# whiskashisei-ver4_1.net
KiCad netlist of a schematic drawn in EAGLE
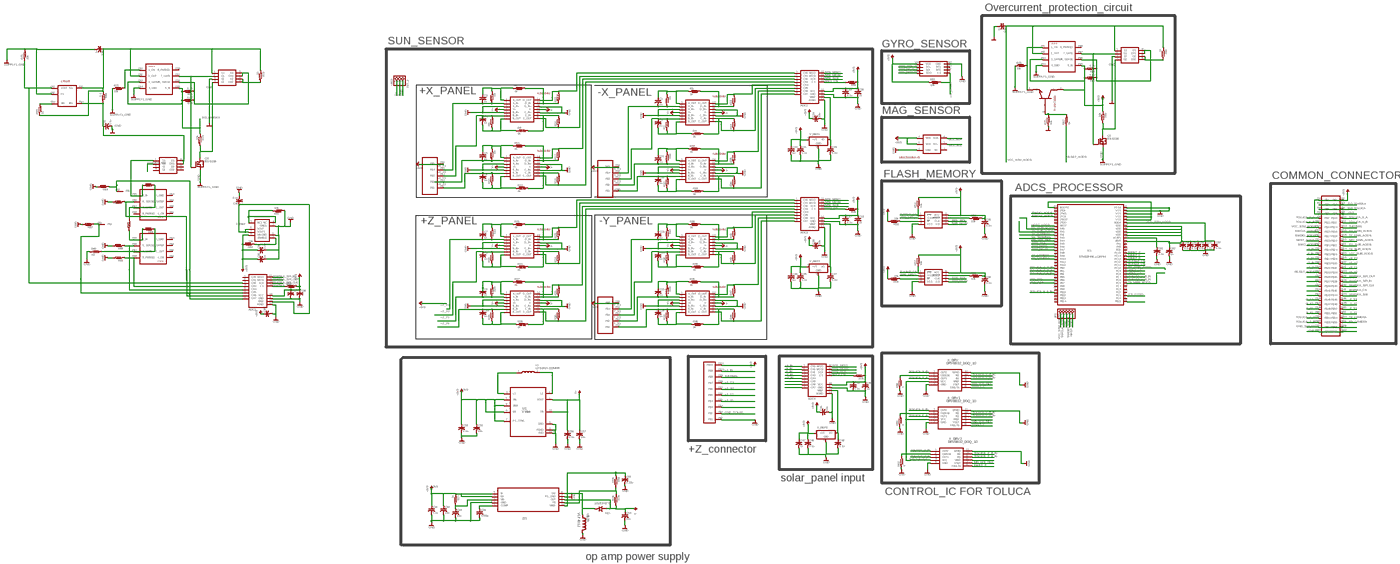
[diagram p0: schematic, sheet 1, overview]
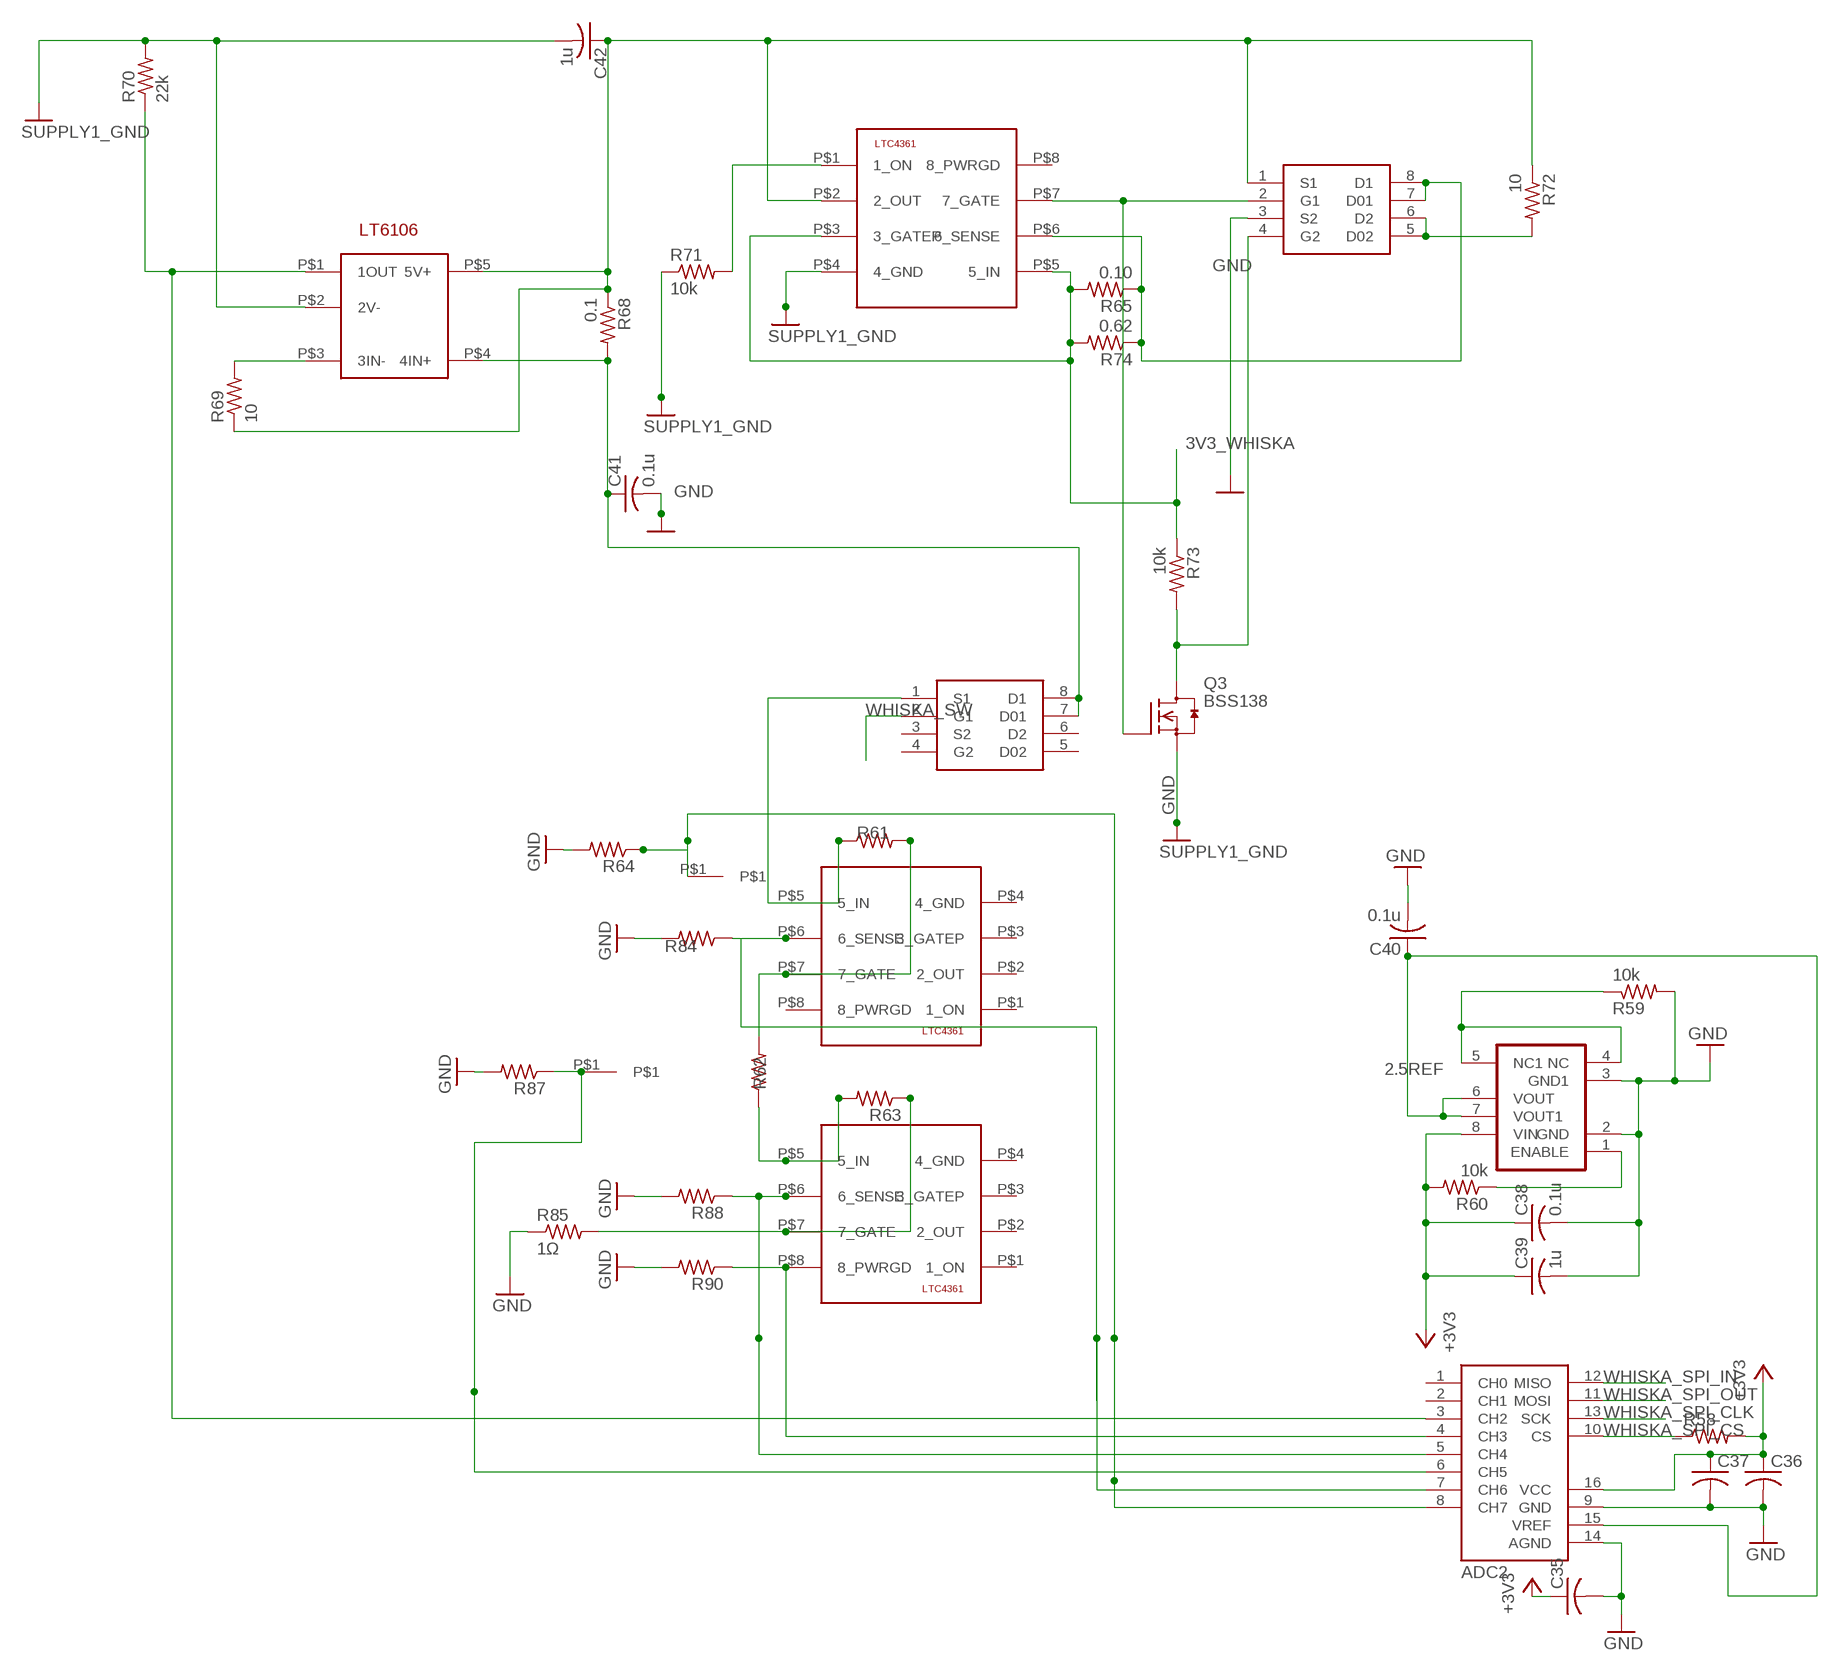
[diagram p1: schematic, sheet 1, part 1 of 4]
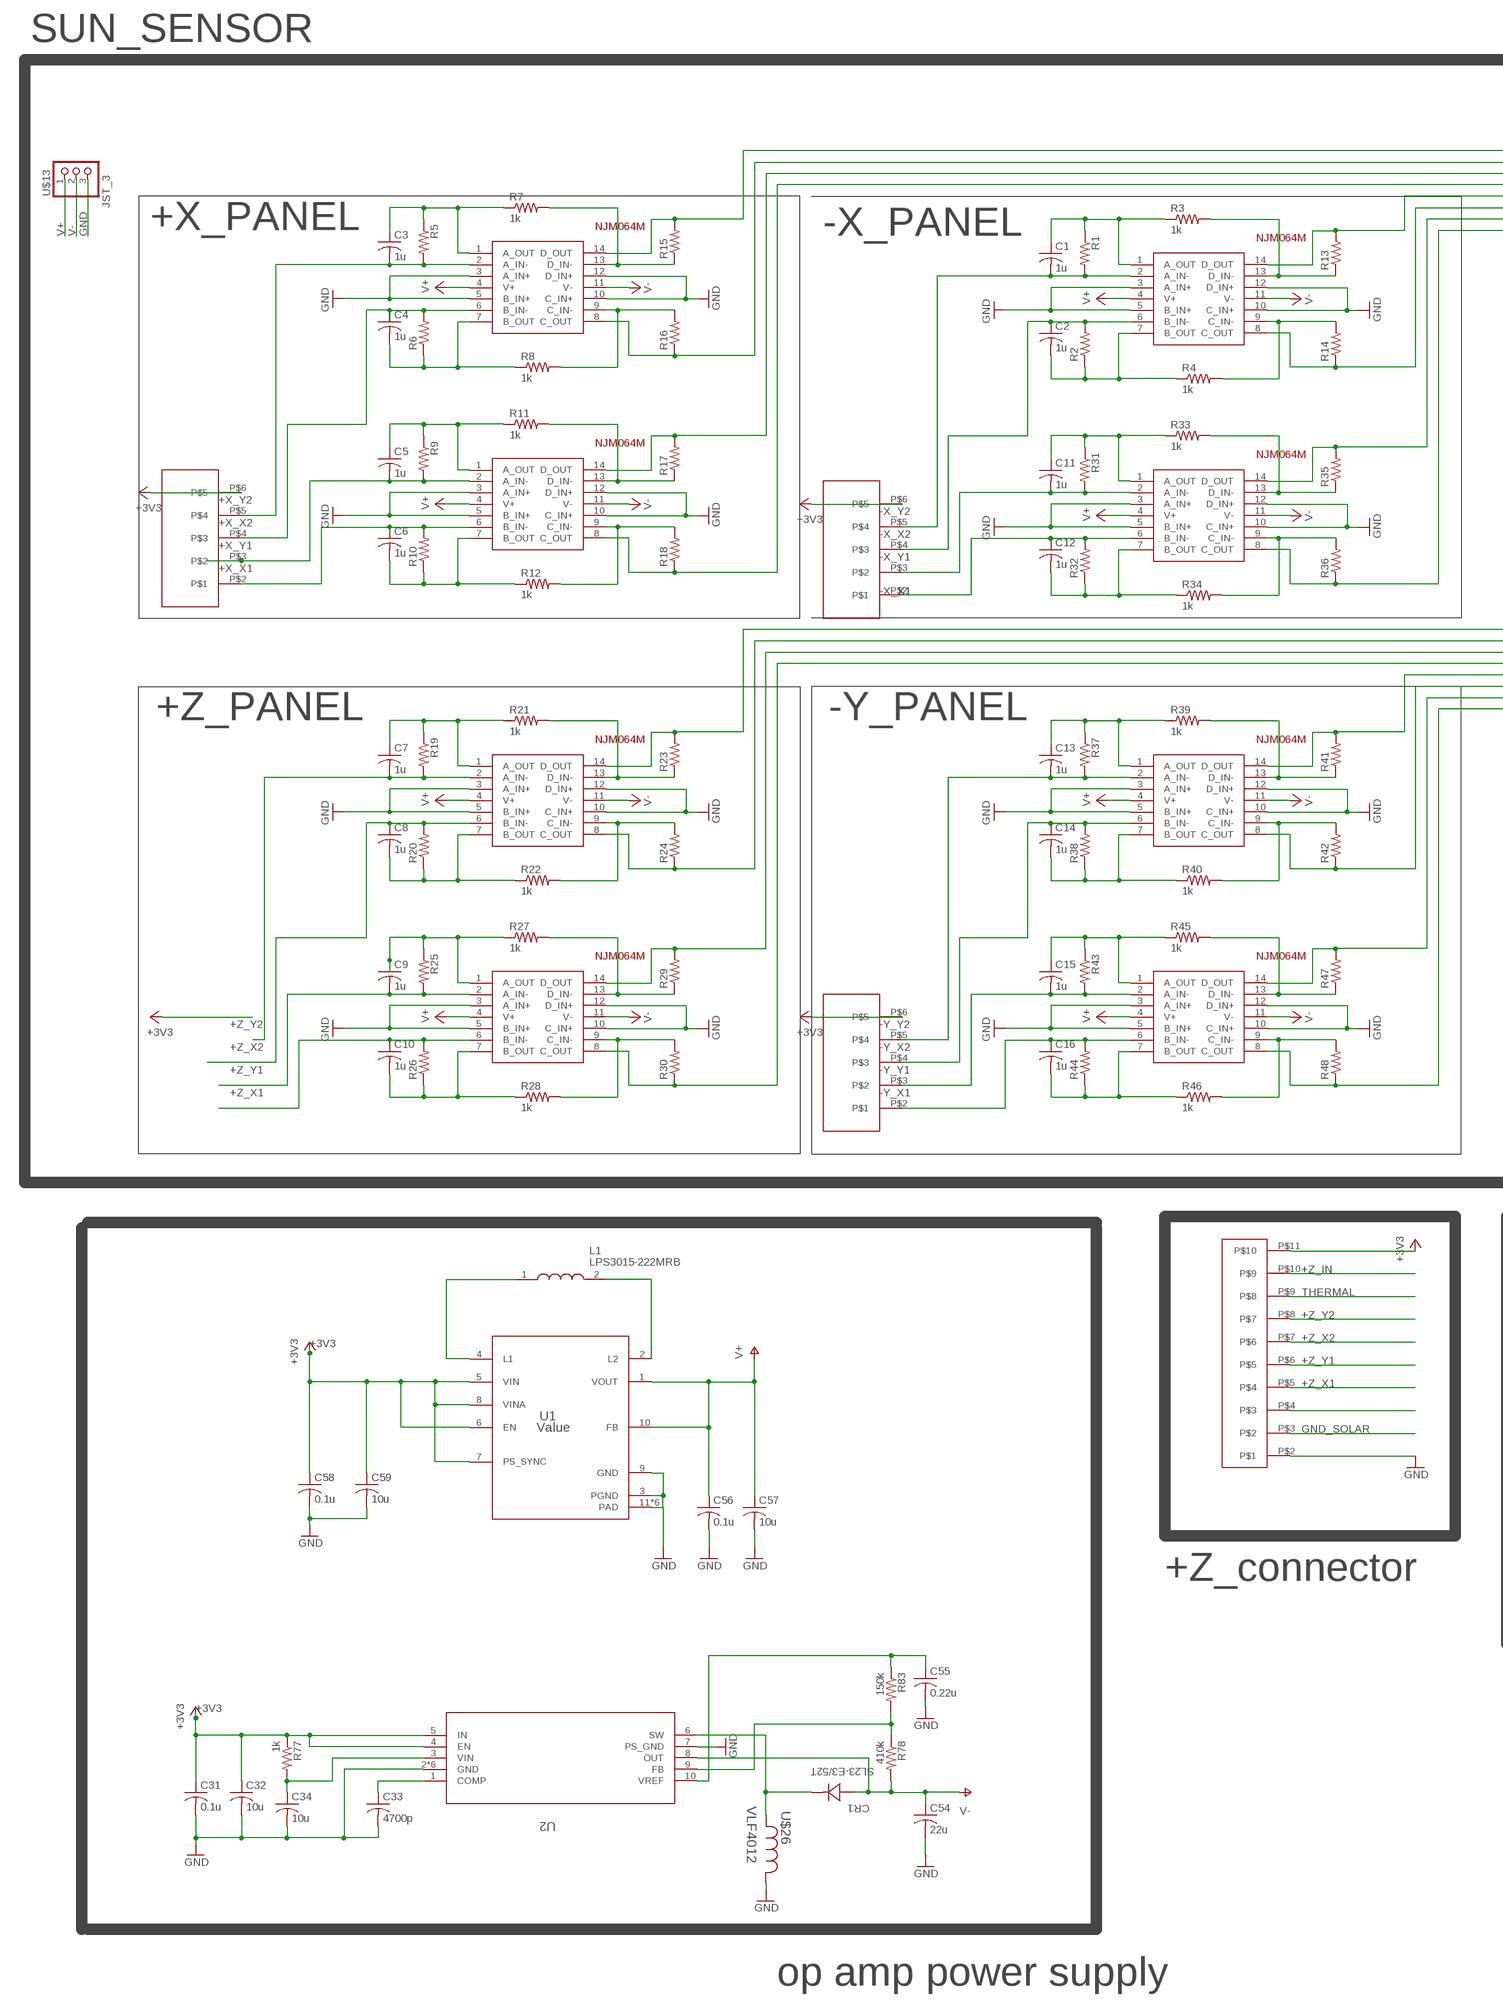
[diagram p2: schematic, sheet 1, part 2 of 4]
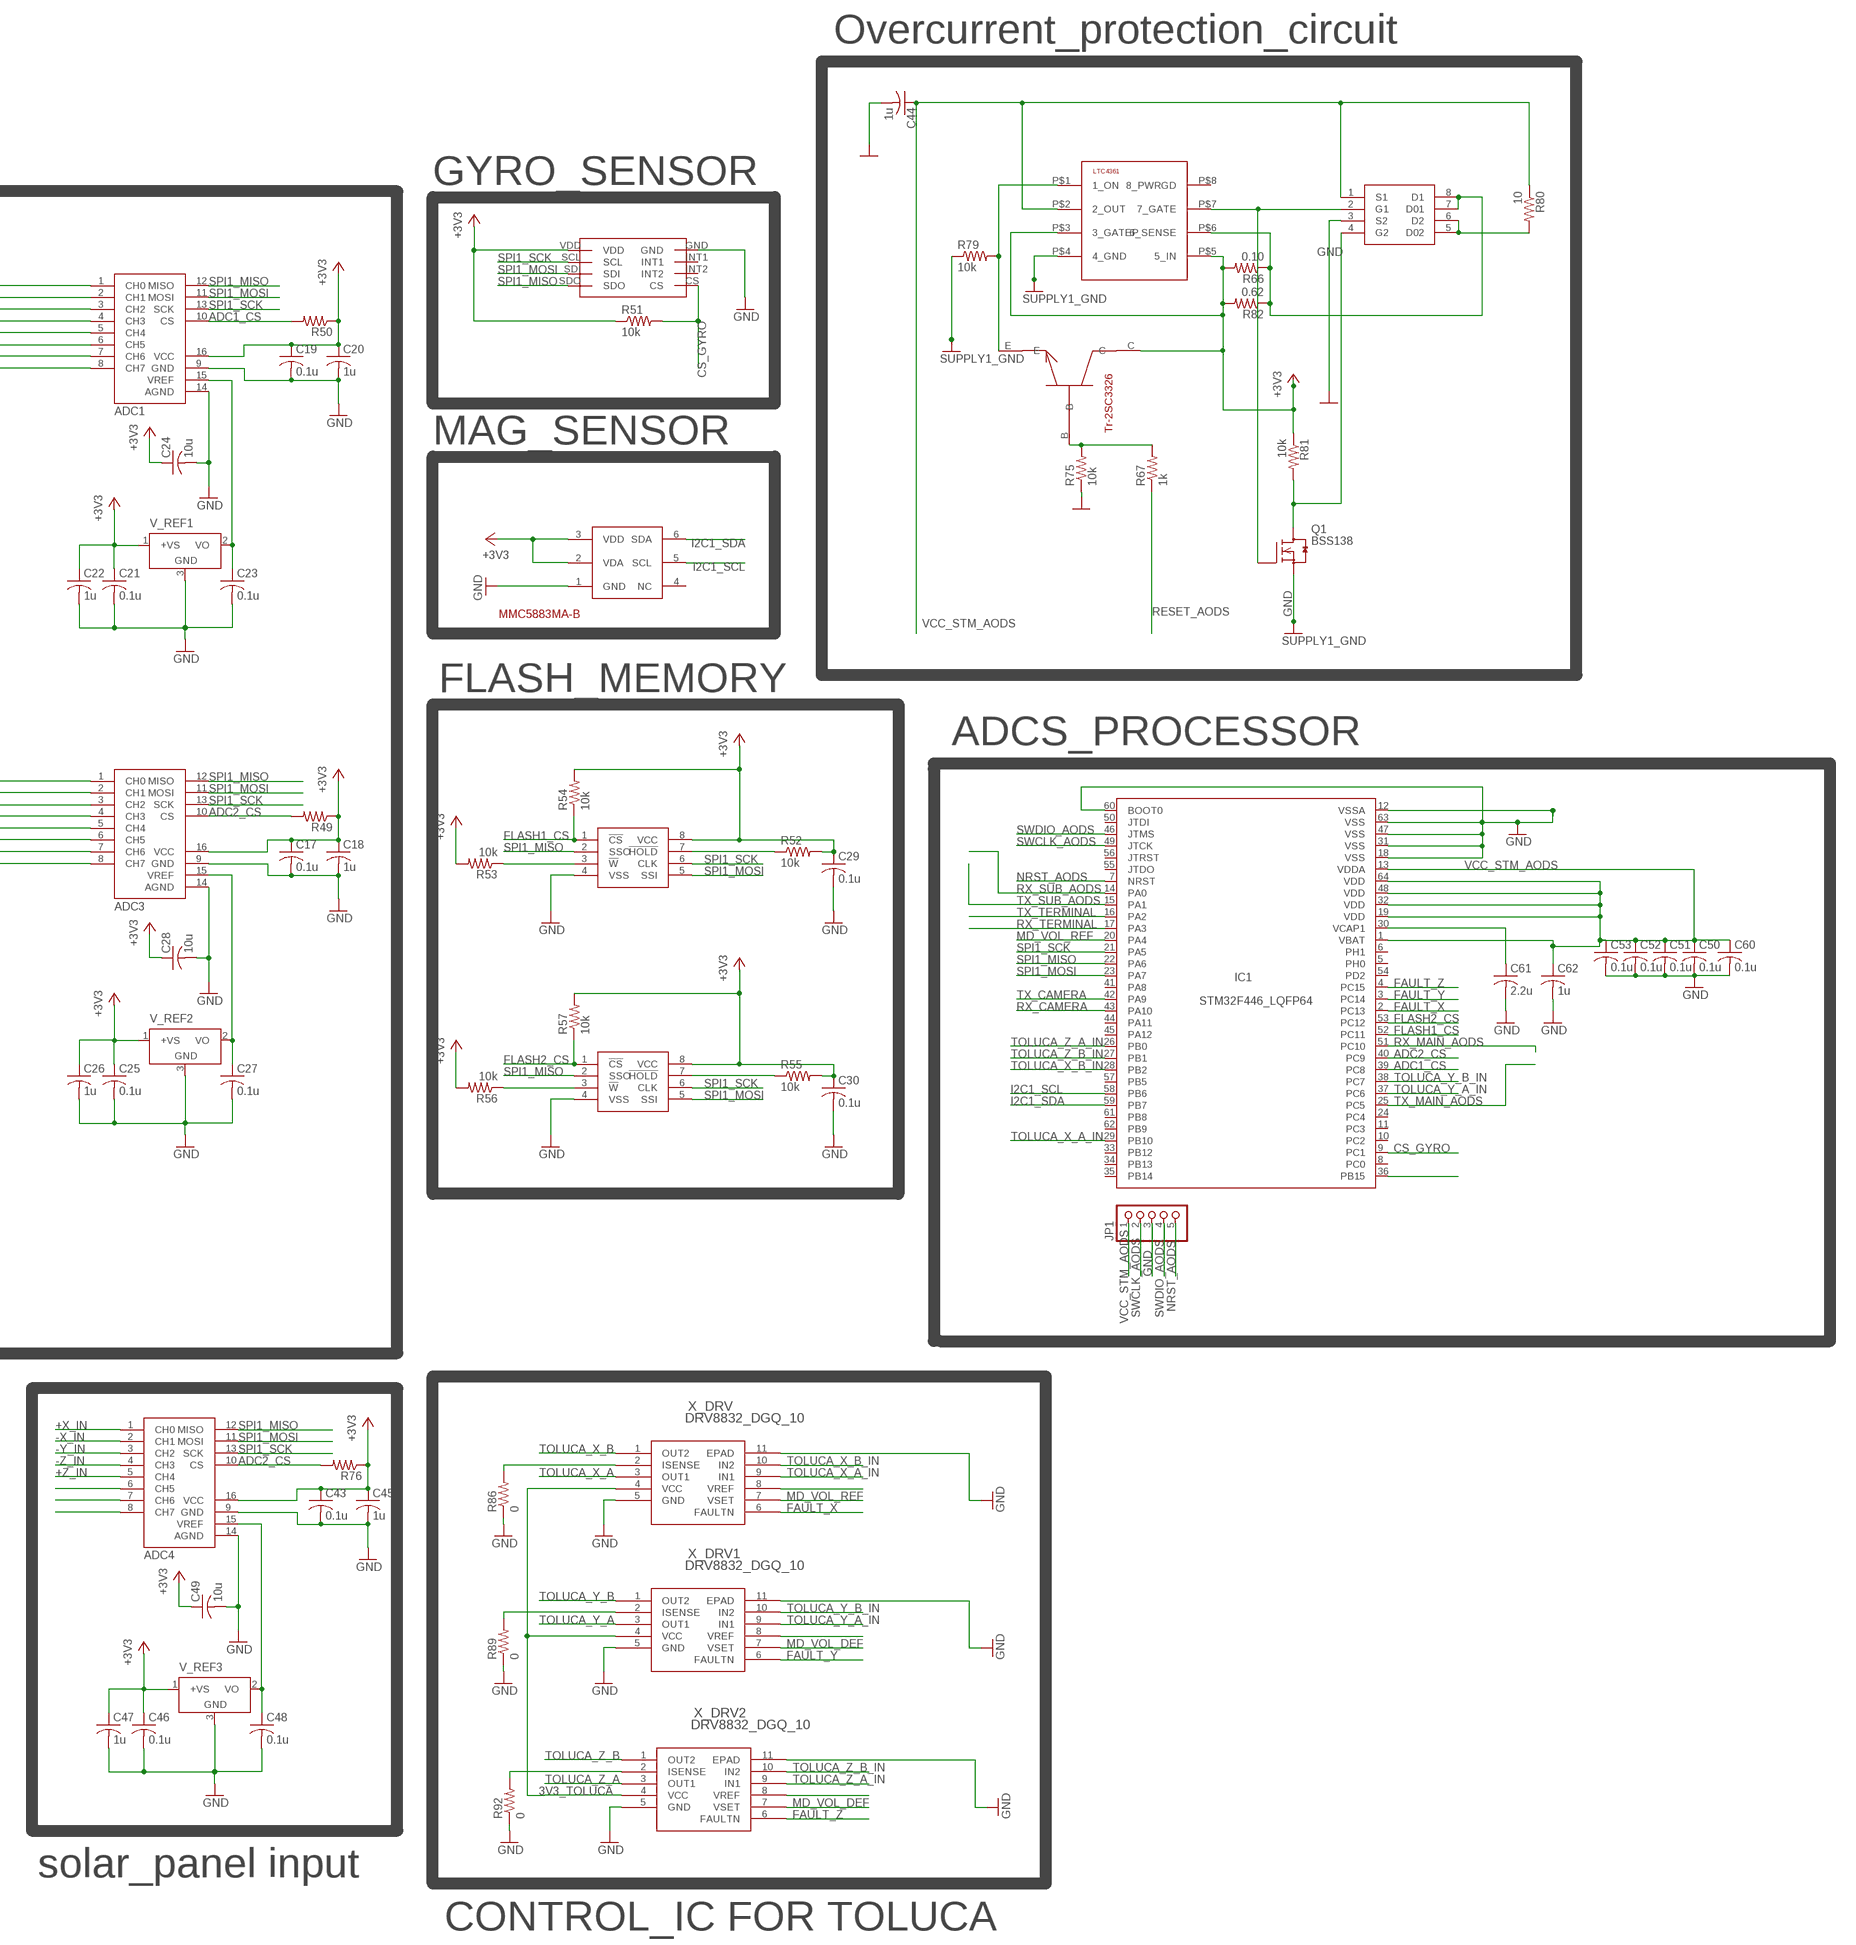
[diagram p3: schematic, sheet 1, part 3 of 4]
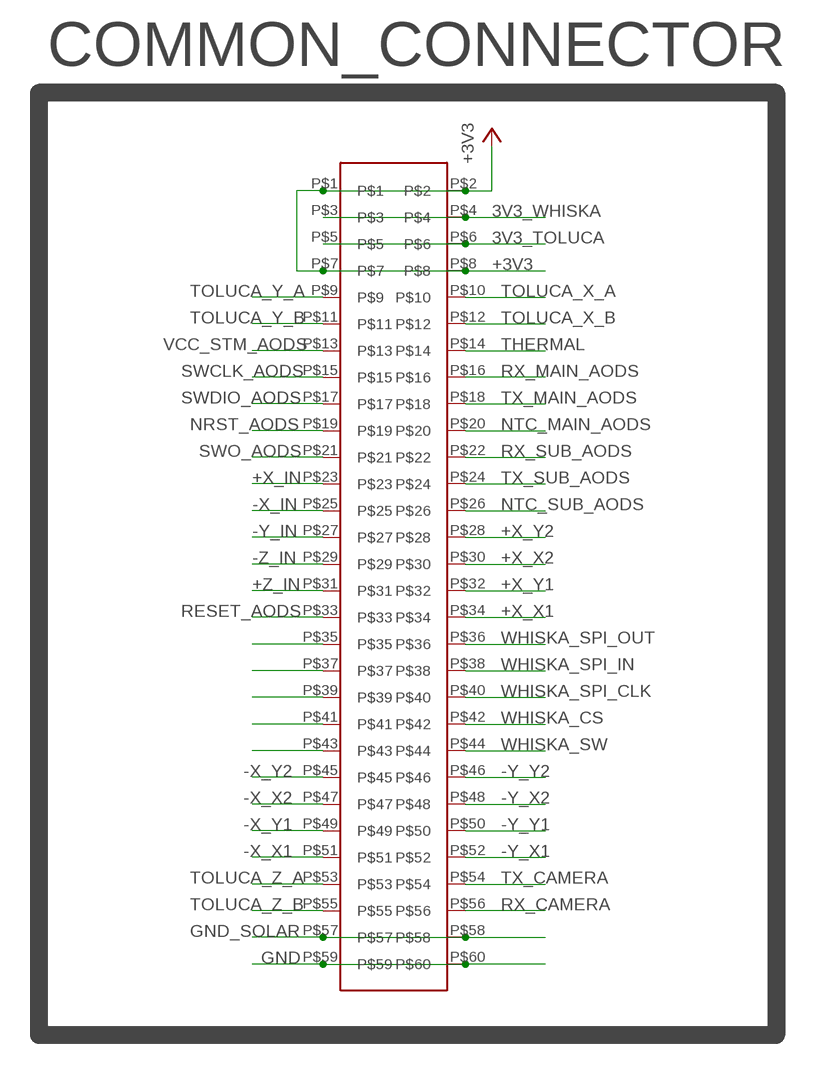
[diagram p4: schematic, sheet 1, part 4 of 4]

(export (version "E")
  (design (tool "Eeschema 10.0.6"))
  (components
    (comp (ref "ADC1")
      (value "ADC_MCP3208")
      (footprint "eagle-import:SO16")
      (libsource (lib "eagle-import") (part "ADC_MCP3208"))
    )
    (comp (ref "ADC2")
      (value "ADC_MCP3208")
      (footprint "eagle-import:SO16")
      (libsource (lib "eagle-import") (part "ADC_MCP3208"))
    )
    (comp (ref "ADC3")
      (value "ADC_MCP3208")
      (footprint "eagle-import:SO16")
      (libsource (lib "eagle-import") (part "ADC_MCP3208"))
    )
    (comp (ref "ADC4")
      (value "ADC_MCP3208")
      (footprint "eagle-import:SO16")
      (libsource (lib "eagle-import") (part "ADC_MCP3208"))
    )
    (comp (ref "C1")
      (value "1u")
      (footprint "eagle-import:C2012")
      (libsource (lib "eagle-import") (part "C-USC2012"))
    )
    (comp (ref "C2")
      (value "1u")
      (footprint "eagle-import:C2012")
      (libsource (lib "eagle-import") (part "C-USC2012"))
    )
    (comp (ref "C3")
      (value "1u")
      (footprint "eagle-import:C2012")
      (libsource (lib "eagle-import") (part "C-USC2012"))
    )
    (comp (ref "C4")
      (value "1u")
      (footprint "eagle-import:C2012")
      (libsource (lib "eagle-import") (part "C-USC2012"))
    )
    (comp (ref "C5")
      (value "1u")
      (footprint "eagle-import:C2012")
      (libsource (lib "eagle-import") (part "C-USC2012"))
    )
    (comp (ref "C6")
      (value "1u")
      (footprint "eagle-import:C2012")
      (libsource (lib "eagle-import") (part "C-USC2012"))
    )
    (comp (ref "C7")
      (value "1u")
      (footprint "eagle-import:C2012")
      (libsource (lib "eagle-import") (part "C-USC2012"))
    )
    (comp (ref "C8")
      (value "1u")
      (footprint "eagle-import:C2012")
      (libsource (lib "eagle-import") (part "C-USC2012"))
    )
    (comp (ref "C9")
      (value "1u")
      (footprint "eagle-import:C2012")
      (libsource (lib "eagle-import") (part "C-USC2012"))
    )
    (comp (ref "C10")
      (value "1u")
      (footprint "eagle-import:C2012")
      (libsource (lib "eagle-import") (part "C-USC2012"))
    )
    (comp (ref "C11")
      (value "1u")
      (footprint "eagle-import:C2012")
      (libsource (lib "eagle-import") (part "C-USC2012"))
    )
    (comp (ref "C12")
      (value "1u")
      (footprint "eagle-import:C2012")
      (libsource (lib "eagle-import") (part "C-USC2012"))
    )
    (comp (ref "C13")
      (value "1u")
      (footprint "eagle-import:C2012")
      (libsource (lib "eagle-import") (part "C-USC2012"))
    )
    (comp (ref "C14")
      (value "1u")
      (footprint "eagle-import:C2012")
      (libsource (lib "eagle-import") (part "C-USC2012"))
    )
    (comp (ref "C15")
      (value "1u")
      (footprint "eagle-import:C2012")
      (libsource (lib "eagle-import") (part "C-USC2012"))
    )
    (comp (ref "C16")
      (value "1u")
      (footprint "eagle-import:C2012")
      (libsource (lib "eagle-import") (part "C-USC2012"))
    )
    (comp (ref "C17")
      (value "0.1u")
      (footprint "eagle-import:C2012")
      (libsource (lib "eagle-import") (part "C-USC2012"))
    )
    (comp (ref "C18")
      (value "1u")
      (footprint "eagle-import:C2012")
      (libsource (lib "eagle-import") (part "C-USC2012"))
    )
    (comp (ref "C19")
      (value "0.1u")
      (footprint "eagle-import:C2012")
      (libsource (lib "eagle-import") (part "C-USC2012"))
    )
    (comp (ref "C20")
      (value "1u")
      (footprint "eagle-import:C2012")
      (libsource (lib "eagle-import") (part "C-USC2012"))
    )
    (comp (ref "C21")
      (value "0.1u")
      (footprint "eagle-import:C2012")
      (libsource (lib "eagle-import") (part "C-USC2012"))
    )
    (comp (ref "C22")
      (value "1u")
      (footprint "eagle-import:C2012")
      (libsource (lib "eagle-import") (part "C-USC2012"))
    )
    (comp (ref "C23")
      (value "0.1u")
      (footprint "eagle-import:C2012")
      (libsource (lib "eagle-import") (part "C-USC2012"))
    )
    (comp (ref "C24")
      (value "10u")
      (footprint "eagle-import:C2012")
      (libsource (lib "eagle-import") (part "C-USC2012"))
    )
    (comp (ref "C25")
      (value "0.1u")
      (footprint "eagle-import:C2012")
      (libsource (lib "eagle-import") (part "C-USC2012"))
    )
    (comp (ref "C26")
      (value "1u")
      (footprint "eagle-import:C2012")
      (libsource (lib "eagle-import") (part "C-USC2012"))
    )
    (comp (ref "C27")
      (value "0.1u")
      (footprint "eagle-import:C2012")
      (libsource (lib "eagle-import") (part "C-USC2012"))
    )
    (comp (ref "C28")
      (value "10u")
      (footprint "eagle-import:C2012")
      (libsource (lib "eagle-import") (part "C-USC2012"))
    )
    (comp (ref "C29")
      (value "0.1u")
      (footprint "eagle-import:C2012")
      (libsource (lib "eagle-import") (part "C-USC2012"))
    )
    (comp (ref "C30")
      (value "0.1u")
      (footprint "eagle-import:C2012")
      (libsource (lib "eagle-import") (part "C-USC2012"))
    )
    (comp (ref "C31")
      (value "0.1u")
      (footprint "eagle-import:C2012")
      (libsource (lib "eagle-import") (part "C-USC2012"))
    )
    (comp (ref "C32")
      (value "10u")
      (footprint "eagle-import:C2012")
      (libsource (lib "eagle-import") (part "C-USC2012"))
    )
    (comp (ref "C33")
      (value "4700p")
      (footprint "eagle-import:C2012")
      (libsource (lib "eagle-import") (part "C-USC2012"))
    )
    (comp (ref "C34")
      (value "10u")
      (footprint "eagle-import:C2012")
      (libsource (lib "eagle-import") (part "C-USC2012"))
    )
    (comp (ref "C35")
      (value "C-USC2012")
      (footprint "eagle-import:C2012")
      (libsource (lib "eagle-import") (part "C-USC2012"))
    )
    (comp (ref "C36")
      (value "C-USC2012")
      (footprint "eagle-import:C2012")
      (libsource (lib "eagle-import") (part "C-USC2012"))
    )
    (comp (ref "C37")
      (value "C-USC2012")
      (footprint "eagle-import:C2012")
      (libsource (lib "eagle-import") (part "C-USC2012"))
    )
    (comp (ref "C38")
      (value "0.1u")
      (footprint "eagle-import:C2012")
      (libsource (lib "eagle-import") (part "resistor_C-USC2012"))
    )
    (comp (ref "C39")
      (value "1u")
      (footprint "eagle-import:C2012")
      (libsource (lib "eagle-import") (part "resistor_C-USC2012"))
    )
    (comp (ref "C40")
      (value "0.1u")
      (footprint "eagle-import:C2012")
      (libsource (lib "eagle-import") (part "resistor_C-USC2012"))
    )
    (comp (ref "C41")
      (value "0.1u")
      (footprint "eagle-import:C2012")
      (libsource (lib "eagle-import") (part "resistor_C-USC2012"))
    )
    (comp (ref "C42")
      (value "1u")
      (footprint "eagle-import:C2012")
      (libsource (lib "eagle-import") (part "resistor_C-USC2012"))
    )
    (comp (ref "C43")
      (value "0.1u")
      (footprint "eagle-import:C2012")
      (libsource (lib "eagle-import") (part "C-USC2012"))
    )
    (comp (ref "C44")
      (value "1u")
      (footprint "eagle-import:C2012")
      (libsource (lib "eagle-import") (part "resistor_C-USC2012"))
    )
    (comp (ref "C45")
      (value "1u")
      (footprint "eagle-import:C2012")
      (libsource (lib "eagle-import") (part "C-USC2012"))
    )
    (comp (ref "C46")
      (value "0.1u")
      (footprint "eagle-import:C2012")
      (libsource (lib "eagle-import") (part "C-USC2012"))
    )
    (comp (ref "C47")
      (value "1u")
      (footprint "eagle-import:C2012")
      (libsource (lib "eagle-import") (part "C-USC2012"))
    )
    (comp (ref "C48")
      (value "0.1u")
      (footprint "eagle-import:C2012")
      (libsource (lib "eagle-import") (part "C-USC2012"))
    )
    (comp (ref "C49")
      (value "10u")
      (footprint "eagle-import:C2012")
      (libsource (lib "eagle-import") (part "C-USC2012"))
    )
    (comp (ref "C50")
      (value "0.1u")
      (footprint "eagle-import:C2012")
      (libsource (lib "eagle-import") (part "C-USC2012"))
    )
    (comp (ref "C51")
      (value "0.1u")
      (footprint "eagle-import:C2012")
      (libsource (lib "eagle-import") (part "C-USC2012"))
    )
    (comp (ref "C52")
      (value "0.1u")
      (footprint "eagle-import:C2012")
      (libsource (lib "eagle-import") (part "C-USC2012"))
    )
    (comp (ref "C53")
      (value "0.1u")
      (footprint "eagle-import:C2012")
      (libsource (lib "eagle-import") (part "C-USC2012"))
    )
    (comp (ref "C54")
      (value "22u")
      (footprint "eagle-import:C2012")
      (libsource (lib "eagle-import") (part "C-USC2012"))
    )
    (comp (ref "C55")
      (value "0.22u")
      (footprint "eagle-import:C2012")
      (libsource (lib "eagle-import") (part "C-USC2012"))
    )
    (comp (ref "C56")
      (value "0.1u")
      (footprint "eagle-import:C2012")
      (libsource (lib "eagle-import") (part "C-USC2012"))
    )
    (comp (ref "C57")
      (value "10u")
      (footprint "eagle-import:C2012")
      (libsource (lib "eagle-import") (part "C-USC2012"))
    )
    (comp (ref "C58")
      (value "0.1u")
      (footprint "eagle-import:C2012")
      (libsource (lib "eagle-import") (part "C-USC2012"))
    )
    (comp (ref "C59")
      (value "10u")
      (footprint "eagle-import:C2012")
      (libsource (lib "eagle-import") (part "C-USC2012"))
    )
    (comp (ref "C60")
      (value "0.1u")
      (footprint "eagle-import:C2012")
      (libsource (lib "eagle-import") (part "C-USC2012"))
    )
    (comp (ref "C61")
      (value "2.2u")
      (footprint "eagle-import:C2012")
      (libsource (lib "eagle-import") (part "C-USC2012"))
    )
    (comp (ref "C62")
      (value "1u")
      (footprint "eagle-import:C2012")
      (libsource (lib "eagle-import") (part "C-USC2012"))
    )
    (comp (ref "CR1")
      (value "SL23-E3/52T")
      (footprint "eagle-import:DIODE_DO214AA")
      (fields (field (name "MANUFACTURER_PART_NUMBER") "SL23E352T"))
      (libsource (lib "eagle-import") (part "SL23-E3/52T"))
    )
    (comp (ref "FLASH_CAM")
      (value "MP25P80")
      (footprint "eagle-import:SO-08M")
      (libsource (lib "eagle-import") (part "MP25P80"))
    )
    (comp (ref "FLASH_SENSOR")
      (value "MP25P80")
      (footprint "eagle-import:SO-08M")
      (libsource (lib "eagle-import") (part "MP25P80"))
    )
    (comp (ref "IC1")
      (value "STM32F446_LQFP64")
      (footprint "eagle-import:LQFP64_PACKAGE")
      (libsource (lib "eagle-import") (part "STM32F446_LQFP64"))
    )
    (comp (ref "JP1")
      (value "PINHD-1X5")
      (footprint "eagle-import:1X05")
      (libsource (lib "eagle-import") (part "PINHD-1X5"))
    )
    (comp (ref "L1")
      (value "LPS3015-222MRB")
      (footprint "eagle-import:LPS3015")
      (fields (field (name "MOUSER_PART_NUMBER") "994-LPS3015-222MRB"))
      (libsource (lib "eagle-import") (part "LPS3015-222MRB"))
    )
    (comp (ref "Q1")
      (value "BSS138")
      (footprint "eagle-import:SOT23")
      (libsource (lib "eagle-import") (part "BSS138"))
    )
    (comp (ref "Q3")
      (value "BSS138")
      (footprint "eagle-import:SOT23")
      (libsource (lib "eagle-import") (part "BSS138"))
    )
    (comp (ref "R1")
      (value "R-US_R2012")
      (footprint "eagle-import:R2012")
      (libsource (lib "eagle-import") (part "R-US_R2012"))
    )
    (comp (ref "R2")
      (value "R-US_R2012")
      (footprint "eagle-import:R2012")
      (libsource (lib "eagle-import") (part "R-US_R2012"))
    )
    (comp (ref "R3")
      (value "1k")
      (footprint "eagle-import:R2012")
      (libsource (lib "eagle-import") (part "R-US_R2012"))
    )
    (comp (ref "R4")
      (value "1k")
      (footprint "eagle-import:R2012")
      (libsource (lib "eagle-import") (part "R-US_R2012"))
    )
    (comp (ref "R5")
      (value "R-US_R2012")
      (footprint "eagle-import:R2012")
      (libsource (lib "eagle-import") (part "R-US_R2012"))
    )
    (comp (ref "R6")
      (value "R-US_R2012")
      (footprint "eagle-import:R2012")
      (libsource (lib "eagle-import") (part "R-US_R2012"))
    )
    (comp (ref "R7")
      (value "1k")
      (footprint "eagle-import:R2012")
      (libsource (lib "eagle-import") (part "R-US_R2012"))
    )
    (comp (ref "R8")
      (value "1k")
      (footprint "eagle-import:R2012")
      (libsource (lib "eagle-import") (part "R-US_R2012"))
    )
    (comp (ref "R9")
      (value "R-US_R2012")
      (footprint "eagle-import:R2012")
      (libsource (lib "eagle-import") (part "R-US_R2012"))
    )
    (comp (ref "R10")
      (value "R-US_R2012")
      (footprint "eagle-import:R2012")
      (libsource (lib "eagle-import") (part "R-US_R2012"))
    )
    (comp (ref "R11")
      (value "1k")
      (footprint "eagle-import:R2012")
      (libsource (lib "eagle-import") (part "R-US_R2012"))
    )
    (comp (ref "R12")
      (value "1k")
      (footprint "eagle-import:R2012")
      (libsource (lib "eagle-import") (part "R-US_R2012"))
    )
    (comp (ref "R13")
      (value "R-US_R2012")
      (footprint "eagle-import:R2012")
      (libsource (lib "eagle-import") (part "R-US_R2012"))
    )
    (comp (ref "R14")
      (value "R-US_R2012")
      (footprint "eagle-import:R2012")
      (libsource (lib "eagle-import") (part "R-US_R2012"))
    )
    (comp (ref "R15")
      (value "R-US_R2012")
      (footprint "eagle-import:R2012")
      (libsource (lib "eagle-import") (part "R-US_R2012"))
    )
    (comp (ref "R16")
      (value "R-US_R2012")
      (footprint "eagle-import:R2012")
      (libsource (lib "eagle-import") (part "R-US_R2012"))
    )
    (comp (ref "R17")
      (value "R-US_R2012")
      (footprint "eagle-import:R2012")
      (libsource (lib "eagle-import") (part "R-US_R2012"))
    )
    (comp (ref "R18")
      (value "R-US_R2012")
      (footprint "eagle-import:R2012")
      (libsource (lib "eagle-import") (part "R-US_R2012"))
    )
    (comp (ref "R19")
      (value "R-US_R2012")
      (footprint "eagle-import:R2012")
      (libsource (lib "eagle-import") (part "R-US_R2012"))
    )
    (comp (ref "R20")
      (value "R-US_R2012")
      (footprint "eagle-import:R2012")
      (libsource (lib "eagle-import") (part "R-US_R2012"))
    )
    (comp (ref "R21")
      (value "1k")
      (footprint "eagle-import:R2012")
      (libsource (lib "eagle-import") (part "R-US_R2012"))
    )
    (comp (ref "R22")
      (value "1k")
      (footprint "eagle-import:R2012")
      (libsource (lib "eagle-import") (part "R-US_R2012"))
    )
    (comp (ref "R23")
      (value "R-US_R2012")
      (footprint "eagle-import:R2012")
      (libsource (lib "eagle-import") (part "R-US_R2012"))
    )
    (comp (ref "R24")
      (value "R-US_R2012")
      (footprint "eagle-import:R2012")
      (libsource (lib "eagle-import") (part "R-US_R2012"))
    )
    (comp (ref "R25")
      (value "R-US_R2012")
      (footprint "eagle-import:R2012")
      (libsource (lib "eagle-import") (part "R-US_R2012"))
    )
    (comp (ref "R26")
      (value "R-US_R2012")
      (footprint "eagle-import:R2012")
      (libsource (lib "eagle-import") (part "R-US_R2012"))
    )
    (comp (ref "R27")
      (value "1k")
      (footprint "eagle-import:R2012")
      (libsource (lib "eagle-import") (part "R-US_R2012"))
    )
    (comp (ref "R28")
      (value "1k")
      (footprint "eagle-import:R2012")
      (libsource (lib "eagle-import") (part "R-US_R2012"))
    )
    (comp (ref "R29")
      (value "R-US_R2012")
      (footprint "eagle-import:R2012")
      (libsource (lib "eagle-import") (part "R-US_R2012"))
    )
    (comp (ref "R30")
      (value "R-US_R2012")
      (footprint "eagle-import:R2012")
      (libsource (lib "eagle-import") (part "R-US_R2012"))
    )
    (comp (ref "R31")
      (value "R-US_R2012")
      (footprint "eagle-import:R2012")
      (libsource (lib "eagle-import") (part "R-US_R2012"))
    )
    (comp (ref "R32")
      (value "R-US_R2012")
      (footprint "eagle-import:R2012")
      (libsource (lib "eagle-import") (part "R-US_R2012"))
    )
    (comp (ref "R33")
      (value "1k")
      (footprint "eagle-import:R2012")
      (libsource (lib "eagle-import") (part "R-US_R2012"))
    )
    (comp (ref "R34")
      (value "1k")
      (footprint "eagle-import:R2012")
      (libsource (lib "eagle-import") (part "R-US_R2012"))
    )
    (comp (ref "R35")
      (value "R-US_R2012")
      (footprint "eagle-import:R2012")
      (libsource (lib "eagle-import") (part "R-US_R2012"))
    )
    (comp (ref "R36")
      (value "R-US_R2012")
      (footprint "eagle-import:R2012")
      (libsource (lib "eagle-import") (part "R-US_R2012"))
    )
    (comp (ref "R37")
      (value "R-US_R2012")
      (footprint "eagle-import:R2012")
      (libsource (lib "eagle-import") (part "R-US_R2012"))
    )
    (comp (ref "R38")
      (value "R-US_R2012")
      (footprint "eagle-import:R2012")
      (libsource (lib "eagle-import") (part "R-US_R2012"))
    )
    (comp (ref "R39")
      (value "1k")
      (footprint "eagle-import:R2012")
      (libsource (lib "eagle-import") (part "R-US_R2012"))
    )
    (comp (ref "R40")
      (value "1k")
      (footprint "eagle-import:R2012")
      (libsource (lib "eagle-import") (part "R-US_R2012"))
    )
    (comp (ref "R41")
      (value "R-US_R2012")
      (footprint "eagle-import:R2012")
      (libsource (lib "eagle-import") (part "R-US_R2012"))
    )
    (comp (ref "R42")
      (value "R-US_R2012")
      (footprint "eagle-import:R2012")
      (libsource (lib "eagle-import") (part "R-US_R2012"))
    )
    (comp (ref "R43")
      (value "R-US_R2012")
      (footprint "eagle-import:R2012")
      (libsource (lib "eagle-import") (part "R-US_R2012"))
    )
    (comp (ref "R44")
      (value "R-US_R2012")
      (footprint "eagle-import:R2012")
      (libsource (lib "eagle-import") (part "R-US_R2012"))
    )
    (comp (ref "R45")
      (value "1k")
      (footprint "eagle-import:R2012")
      (libsource (lib "eagle-import") (part "R-US_R2012"))
    )
    (comp (ref "R46")
      (value "1k")
      (footprint "eagle-import:R2012")
      (libsource (lib "eagle-import") (part "R-US_R2012"))
    )
    (comp (ref "R47")
      (value "R-US_R2012")
      (footprint "eagle-import:R2012")
      (libsource (lib "eagle-import") (part "R-US_R2012"))
    )
    (comp (ref "R48")
      (value "R-US_R2012")
      (footprint "eagle-import:R2012")
      (libsource (lib "eagle-import") (part "R-US_R2012"))
    )
    (comp (ref "R49")
      (value "R-US_R2012")
      (footprint "eagle-import:R2012")
      (libsource (lib "eagle-import") (part "R-US_R2012"))
    )
    (comp (ref "R50")
      (value "R-US_R2012")
      (footprint "eagle-import:R2012")
      (libsource (lib "eagle-import") (part "R-US_R2012"))
    )
    (comp (ref "R51")
      (value "10k")
      (footprint "eagle-import:R2012")
      (libsource (lib "eagle-import") (part "R-US_R2012"))
    )
    (comp (ref "R52")
      (value "10k")
      (footprint "eagle-import:R2012")
      (libsource (lib "eagle-import") (part "R-US_R2012"))
    )
    (comp (ref "R53")
      (value "10k")
      (footprint "eagle-import:R2012")
      (libsource (lib "eagle-import") (part "R-US_R2012"))
    )
    (comp (ref "R54")
      (value "10k")
      (footprint "eagle-import:R2012")
      (libsource (lib "eagle-import") (part "R-US_R2012"))
    )
    (comp (ref "R55")
      (value "10k")
      (footprint "eagle-import:R2012")
      (libsource (lib "eagle-import") (part "R-US_R2012"))
    )
    (comp (ref "R56")
      (value "10k")
      (footprint "eagle-import:R2012")
      (libsource (lib "eagle-import") (part "R-US_R2012"))
    )
    (comp (ref "R57")
      (value "10k")
      (footprint "eagle-import:R2012")
      (libsource (lib "eagle-import") (part "R-US_R2012"))
    )
    (comp (ref "R58")
      (value "R-US_R2012")
      (footprint "eagle-import:R2012")
      (libsource (lib "eagle-import") (part "R-US_R2012"))
    )
    (comp (ref "R59")
      (value "10k")
      (footprint "eagle-import:R2012")
      (libsource (lib "eagle-import") (part "resistor_R-US_R2012"))
    )
    (comp (ref "R60")
      (value "10k")
      (footprint "eagle-import:R2012")
      (libsource (lib "eagle-import") (part "resistor_R-US_R2012"))
    )
    (comp (ref "R61")
      (value "R-US_R2012")
      (footprint "eagle-import:R2012")
      (libsource (lib "eagle-import") (part "R-US_R2012"))
    )
    (comp (ref "R62")
      (value "R-US_R2012")
      (footprint "eagle-import:R2012")
      (libsource (lib "eagle-import") (part "R-US_R2012"))
    )
    (comp (ref "R63")
      (value "R-US_R2012")
      (footprint "eagle-import:R2012")
      (libsource (lib "eagle-import") (part "R-US_R2012"))
    )
    (comp (ref "R64")
      (value "R-US_R2012")
      (footprint "eagle-import:R2012")
      (libsource (lib "eagle-import") (part "R-US_R2012"))
    )
    (comp (ref "R65")
      (value "0.10")
      (footprint "eagle-import:R2012")
      (libsource (lib "eagle-import") (part "resistor_R-US_R2012"))
    )
    (comp (ref "R66")
      (value "0.10")
      (footprint "eagle-import:R2012")
      (libsource (lib "eagle-import") (part "resistor_R-US_R2012"))
    )
    (comp (ref "R67")
      (value "1k")
      (footprint "eagle-import:R2012")
      (libsource (lib "eagle-import") (part "resistor_R-US_R2012"))
    )
    (comp (ref "R68")
      (value "0.1")
      (footprint "eagle-import:R2012")
      (libsource (lib "eagle-import") (part "resistor_R-US_R2012"))
    )
    (comp (ref "R69")
      (value "10")
      (footprint "eagle-import:R2012")
      (libsource (lib "eagle-import") (part "resistor_R-US_R2012"))
    )
    (comp (ref "R70")
      (value "22k")
      (footprint "eagle-import:R2012")
      (libsource (lib "eagle-import") (part "resistor_R-US_R2012"))
    )
    (comp (ref "R71")
      (value "10k")
      (footprint "eagle-import:R2012")
      (libsource (lib "eagle-import") (part "resistor_R-US_R2012"))
    )
    (comp (ref "R72")
      (value "10")
      (footprint "eagle-import:R2012")
      (libsource (lib "eagle-import") (part "resistor_R-US_R2012"))
    )
    (comp (ref "R73")
      (value "10k")
      (footprint "eagle-import:R2012")
      (libsource (lib "eagle-import") (part "resistor_R-US_R2012"))
    )
    (comp (ref "R74")
      (value "0.62")
      (footprint "eagle-import:R2012")
      (libsource (lib "eagle-import") (part "resistor_R-US_R2012"))
    )
    (comp (ref "R75")
      (value "10k")
      (footprint "eagle-import:R2012")
      (libsource (lib "eagle-import") (part "resistor_R-US_R2012"))
    )
    (comp (ref "R76")
      (value "R-US_R2012")
      (footprint "eagle-import:R2012")
      (libsource (lib "eagle-import") (part "R-US_R2012"))
    )
    (comp (ref "R77")
      (value "1k")
      (footprint "eagle-import:R2012")
      (libsource (lib "eagle-import") (part "R-US_R2012"))
    )
    (comp (ref "R78")
      (value "410k")
      (footprint "eagle-import:R2012")
      (libsource (lib "eagle-import") (part "R-US_R2012"))
    )
    (comp (ref "R79")
      (value "10k")
      (footprint "eagle-import:R2012")
      (libsource (lib "eagle-import") (part "resistor_R-US_R2012"))
    )
    (comp (ref "R80")
      (value "10")
      (footprint "eagle-import:R2012")
      (libsource (lib "eagle-import") (part "resistor_R-US_R2012"))
    )
    (comp (ref "R81")
      (value "10k")
      (footprint "eagle-import:R2012")
      (libsource (lib "eagle-import") (part "resistor_R-US_R2012"))
    )
    (comp (ref "R82")
      (value "0.62")
      (footprint "eagle-import:R2012")
      (libsource (lib "eagle-import") (part "resistor_R-US_R2012"))
    )
    (comp (ref "R83")
      (value "150k")
      (footprint "eagle-import:R2012")
      (libsource (lib "eagle-import") (part "R-US_R2012"))
    )
    (comp (ref "R84")
      (value "R-US_R2012")
      (footprint "eagle-import:R2012")
      (libsource (lib "eagle-import") (part "R-US_R2012"))
    )
    (comp (ref "R85")
      (value "1Ω")
      (footprint "eagle-import:R2012")
      (libsource (lib "eagle-import") (part "R-US_R2012"))
    )
    (comp (ref "R86")
      (value "0")
      (footprint "eagle-import:R2012")
      (libsource (lib "eagle-import") (part "R-US_R2012"))
    )
    (comp (ref "R87")
      (value "R-US_R2012")
      (footprint "eagle-import:R2012")
      (libsource (lib "eagle-import") (part "R-US_R2012"))
    )
    (comp (ref "R88")
      (value "R-US_R2012")
      (footprint "eagle-import:R2012")
      (libsource (lib "eagle-import") (part "R-US_R2012"))
    )
    (comp (ref "R89")
      (value "0")
      (footprint "eagle-import:R2012")
      (libsource (lib "eagle-import") (part "R-US_R2012"))
    )
    (comp (ref "R90")
      (value "R-US_R2012")
      (footprint "eagle-import:R2012")
      (libsource (lib "eagle-import") (part "R-US_R2012"))
    )
    (comp (ref "R92")
      (value "0")
      (footprint "eagle-import:R2012")
      (libsource (lib "eagle-import") (part "R-US_R2012"))
    )
    (comp (ref "U$1")
      (value "1.27_60")
      (footprint "eagle-import:1.27_60")
      (libsource (lib "eagle-import") (part "1.27_60"))
    )
    (comp (ref "U$3")
      (value "MMC5883MA-B")
      (footprint "eagle-import:MMC5883MA-B")
      (libsource (lib "eagle-import") (part "MMC5883MA-B"))
    )
    (comp (ref "U$4")
      (value "L3GD20_SET")
      (footprint "eagle-import:L3GD20_SET")
      (libsource (lib "eagle-import") (part "L3GD20_SET"))
    )
    (comp (ref "U$5")
      (value "NJM064M")
      (footprint "eagle-import:NJM064M")
      (libsource (lib "eagle-import") (part "NJM064M"))
    )
    (comp (ref "U$6")
      (value "NJM064M")
      (footprint "eagle-import:NJM064M")
      (libsource (lib "eagle-import") (part "NJM064M"))
    )
    (comp (ref "U$7")
      (value "NJM064M")
      (footprint "eagle-import:NJM064M")
      (libsource (lib "eagle-import") (part "NJM064M"))
    )
    (comp (ref "U$8")
      (value "NJM064M")
      (footprint "eagle-import:NJM064M")
      (libsource (lib "eagle-import") (part "NJM064M"))
    )
    (comp (ref "U$9")
      (value "NJM064M")
      (footprint "eagle-import:NJM064M")
      (libsource (lib "eagle-import") (part "NJM064M"))
    )
    (comp (ref "U$10")
      (value "NJM064M")
      (footprint "eagle-import:NJM064M")
      (libsource (lib "eagle-import") (part "NJM064M"))
    )
    (comp (ref "U$11")
      (value "NJM064M")
      (footprint "eagle-import:NJM064M")
      (libsource (lib "eagle-import") (part "NJM064M"))
    )
    (comp (ref "U$12")
      (value "NJM064M")
      (footprint "eagle-import:NJM064M")
      (libsource (lib "eagle-import") (part "NJM064M"))
    )
    (comp (ref "U$13")
      (value "JST_3")
      (footprint "eagle-import:JST_3")
      (libsource (lib "eagle-import") (part "JST_3"))
    )
    (comp (ref "U$14")
      (value "ADR3525")
      (footprint "eagle-import:ADR3525")
      (libsource (lib "eagle-import") (part "ADR3525"))
    )
    (comp (ref "U$15")
      (value "LTC4361")
      (footprint "eagle-import:LTC4361_2")
      (libsource (lib "eagle-import") (part "LTC4361"))
    )
    (comp (ref "U$16")
      (value "IRF7910")
      (footprint "eagle-import:SO-08")
      (libsource (lib "eagle-import") (part "IRF7910"))
    )
    (comp (ref "U$17")
      (value "LTC4361")
      (footprint "eagle-import:LTC4361_2")
      (libsource (lib "eagle-import") (part "LTC4361"))
    )
    (comp (ref "U$18")
      (value "LT6106")
      (footprint "eagle-import:LT6106")
      (libsource (lib "eagle-import") (part "LT6106"))
    )
    (comp (ref "U$19")
      (value "IRF7910")
      (footprint "eagle-import:SO-08")
      (libsource (lib "eagle-import") (part "IRF7910"))
    )
    (comp (ref "U$20")
      (value "TR-NPN-2SC3326")
      (footprint "eagle-import:TR-NPN-2SC3326")
      (libsource (lib "eagle-import") (part "TR-NPN-2SC3326"))
    )
    (comp (ref "U$21")
      (value "JST_1MM_10")
      (footprint "eagle-import:JST_1MM_10")
      (libsource (lib "eagle-import") (part "JST_1MM_10"))
    )
    (comp (ref "U$22")
      (value "IRF7910")
      (footprint "eagle-import:SO-08")
      (libsource (lib "eagle-import") (part "IRF7910"))
    )
    (comp (ref "U$23")
      (value "LTC4361")
      (footprint "eagle-import:LTC4361_2")
      (libsource (lib "eagle-import") (part "LTC4361"))
    )
    (comp (ref "U$26")
      (value "VLF4012")
      (footprint "eagle-import:IND_4012")
      (libsource (lib "eagle-import") (part "VLF4012"))
    )
    (comp (ref "U$27")
      (value "LTC4361")
      (footprint "eagle-import:LTC4361_2")
      (libsource (lib "eagle-import") (part "LTC4361"))
    )
    (comp (ref "U$31")
      (value "JST_1MM_5")
      (footprint "eagle-import:JST_1MM_5")
      (libsource (lib "eagle-import") (part "JST_1MM_5"))
    )
    (comp (ref "U$32")
      (value "JST_1MM_5")
      (footprint "eagle-import:JST_1MM_5")
      (libsource (lib "eagle-import") (part "JST_1MM_5"))
    )
    (comp (ref "U$34")
      (value "JST_1MM_5")
      (footprint "eagle-import:JST_1MM_5")
      (libsource (lib "eagle-import") (part "JST_1MM_5"))
    )
    (comp (ref "U1")
      (value "Value")
      (footprint "eagle-import:DRC0010A")
      (fields (field (name "MANUFACTURER") "Texas Instruments") (field (name "PARTNUMBER") "TPS63000DRC"))
      (libsource (lib "eagle-import") (part "TPS63000DRCR"))
    )
    (comp (ref "U2")
      (value "TPS63700DRCRG4")
      (footprint "eagle-import:DRC10_2P4X1P65")
      (libsource (lib "eagle-import") (part "TPS63700DRCRG4"))
    )
    (comp (ref "V_REF1")
      (value "LM50")
      (footprint "eagle-import:SOT23")
      (libsource (lib "eagle-import") (part "LM50"))
    )
    (comp (ref "V_REF2")
      (value "LM50")
      (footprint "eagle-import:SOT23")
      (libsource (lib "eagle-import") (part "LM50"))
    )
    (comp (ref "V_REF3")
      (value "LM50")
      (footprint "eagle-import:SOT23")
      (libsource (lib "eagle-import") (part "LM50"))
    )
    (comp (ref "WHISKAPAD1")
      (value "WHISKAPAD")
      (footprint "eagle-import:LTC4361_2")
      (libsource (lib "eagle-import") (part "WHISKAPAD"))
    )
    (comp (ref "WHISKAPAD2")
      (value "WHISKAPAD")
      (footprint "eagle-import:LTC4361_2")
      (libsource (lib "eagle-import") (part "WHISKAPAD"))
    )
    (comp (ref "X_DRV")
      (value "DRV8832_DGQ_10")
      (footprint "eagle-import:DGQ10_2P18X1P72")
      (fields
        (field (name "GENERIC_PART_NUMBER") "DRV8832")
        (field (name "MANUFACTURER") "Texas Instruments")
        (field (name "MANUFACTURER_PART_NUMBER") "drv8832_dgq_10")
      )
      (libsource (lib "eagle-import") (part "DRV8832_DGQ_10"))
    )
    (comp (ref "X_DRV1")
      (value "DRV8832_DGQ_10")
      (footprint "eagle-import:DGQ10_2P18X1P72")
      (fields
        (field (name "GENERIC_PART_NUMBER") "DRV8832")
        (field (name "MANUFACTURER") "Texas Instruments")
        (field (name "MANUFACTURER_PART_NUMBER") "drv8832_dgq_10")
      )
      (libsource (lib "eagle-import") (part "DRV8832_DGQ_10"))
    )
    (comp (ref "X_DRV2")
      (value "DRV8832_DGQ_10")
      (footprint "eagle-import:DGQ10_2P18X1P72")
      (fields
        (field (name "GENERIC_PART_NUMBER") "DRV8832")
        (field (name "MANUFACTURER") "Texas Instruments")
        (field (name "MANUFACTURER_PART_NUMBER") "drv8832_dgq_10")
      )
      (libsource (lib "eagle-import") (part "DRV8832_DGQ_10"))
    )
  )
  (nets
    (net (code "1") (name "+3V3") (class "Default")
      (node (ref "ADC1") (pin "16") (pinfunction "VCC_16") (pintype "power_in"))
      (node (ref "ADC2") (pin "16") (pinfunction "VCC_16") (pintype "power_in"))
      (node (ref "ADC3") (pin "16") (pinfunction "VCC_16") (pintype "power_in"))
      (node (ref "ADC4") (pin "16") (pinfunction "VCC_16") (pintype "power_in"))
      (node (ref "C17") (pin "1") (pinfunction "1_1") (pintype "passive"))
      (node (ref "C18") (pin "1") (pinfunction "1_1") (pintype "passive"))
      (node (ref "C19") (pin "1") (pinfunction "1_1") (pintype "passive"))
      (node (ref "C20") (pin "1") (pinfunction "1_1") (pintype "passive"))
      (node (ref "C21") (pin "1") (pinfunction "1_1") (pintype "passive"))
      (node (ref "C22") (pin "1") (pinfunction "1_1") (pintype "passive"))
      (node (ref "C24") (pin "1") (pinfunction "1_1") (pintype "passive"))
      (node (ref "C25") (pin "1") (pinfunction "1_1") (pintype "passive"))
      (node (ref "C26") (pin "1") (pinfunction "1_1") (pintype "passive"))
      (node (ref "C28") (pin "1") (pinfunction "1_1") (pintype "passive"))
      (node (ref "C29") (pin "1") (pinfunction "1_1") (pintype "passive"))
      (node (ref "C30") (pin "1") (pinfunction "1_1") (pintype "passive"))
      (node (ref "C31") (pin "1") (pinfunction "1_1") (pintype "passive"))
      (node (ref "C32") (pin "1") (pinfunction "1_1") (pintype "passive"))
      (node (ref "C35") (pin "1") (pinfunction "1_1") (pintype "passive"))
      (node (ref "C36") (pin "1") (pinfunction "1_1") (pintype "passive"))
      (node (ref "C37") (pin "1") (pinfunction "1_1") (pintype "passive"))
      (node (ref "C38") (pin "1") (pinfunction "1_1") (pintype "passive"))
      (node (ref "C39") (pin "1") (pinfunction "1_1") (pintype "passive"))
      (node (ref "C43") (pin "1") (pinfunction "1_1") (pintype "passive"))
      (node (ref "C45") (pin "1") (pinfunction "1_1") (pintype "passive"))
      (node (ref "C46") (pin "1") (pinfunction "1_1") (pintype "passive"))
      (node (ref "C47") (pin "1") (pinfunction "1_1") (pintype "passive"))
      (node (ref "C49") (pin "1") (pinfunction "1_1") (pintype "passive"))
      (node (ref "C58") (pin "1") (pinfunction "1_1") (pintype "passive"))
      (node (ref "C59") (pin "1") (pinfunction "1_1") (pintype "passive"))
      (node (ref "FLASH_CAM") (pin "8") (pinfunction "VCC_8") (pintype "power_in"))
      (node (ref "FLASH_SENSOR") (pin "8") (pinfunction "VCC_8") (pintype "power_in"))
      (node (ref "R49") (pin "1") (pinfunction "1_1") (pintype "passive"))
      (node (ref "R50") (pin "1") (pinfunction "1_1") (pintype "passive"))
      (node (ref "R51") (pin "1") (pinfunction "1_1") (pintype "passive"))
      (node (ref "R52") (pin "2") (pinfunction "2_2") (pintype "passive"))
      (node (ref "R53") (pin "2") (pinfunction "2_2") (pintype "passive"))
      (node (ref "R54") (pin "2") (pinfunction "2_2") (pintype "passive"))
      (node (ref "R55") (pin "2") (pinfunction "2_2") (pintype "passive"))
      (node (ref "R56") (pin "2") (pinfunction "2_2") (pintype "passive"))
      (node (ref "R57") (pin "2") (pinfunction "2_2") (pintype "passive"))
      (node (ref "R58") (pin "2") (pinfunction "2_2") (pintype "passive"))
      (node (ref "R60") (pin "2") (pinfunction "2_2") (pintype "passive"))
      (node (ref "R66") (pin "2") (pinfunction "2_2") (pintype "passive"))
      (node (ref "R76") (pin "1") (pinfunction "1_1") (pintype "passive"))
      (node (ref "R77") (pin "1") (pinfunction "1_1") (pintype "passive"))
      (node (ref "R81") (pin "1") (pinfunction "1_1") (pintype "passive"))
      (node (ref "R82") (pin "2") (pinfunction "2_2") (pintype "passive"))
      (node (ref "U$1") (pin "P$1") (pinfunction "P$1_P$1") (pintype "bidirectional"))
      (node (ref "U$1") (pin "P$2") (pinfunction "P$2_P$2") (pintype "bidirectional"))
      (node (ref "U$1") (pin "P$7") (pinfunction "P$7_P$7") (pintype "bidirectional"))
      (node (ref "U$1") (pin "P$8") (pinfunction "P$8_P$8") (pintype "bidirectional"))
      (node (ref "U$14") (pin "8") (pinfunction "VIN_8") (pintype "bidirectional"))
      (node (ref "U$17") (pin "P$3") (pinfunction "3_GATEP_P$3") (pintype "bidirectional"))
      (node (ref "U$17") (pin "P$5") (pinfunction "5_IN_P$5") (pintype "bidirectional"))
      (node (ref "U$20") (pin "C") (pinfunction "C_C") (pintype "bidirectional"))
      (node (ref "U$21") (pin "P$11") (pinfunction "P$10_P$11") (pintype "bidirectional"))
      (node (ref "U$3") (pin "2") (pinfunction "VDA_2") (pintype "bidirectional"))
      (node (ref "U$3") (pin "3") (pinfunction "VDD_3") (pintype "bidirectional"))
      (node (ref "U$31") (pin "P$6") (pinfunction "P$5_P$6") (pintype "bidirectional"))
      (node (ref "U$32") (pin "P$6") (pinfunction "P$5_P$6") (pintype "bidirectional"))
      (node (ref "U$34") (pin "P$6") (pinfunction "P$5_P$6") (pintype "bidirectional"))
      (node (ref "U$4") (pin "VDD") (pinfunction "VDD_VDD") (pintype "bidirectional"))
      (node (ref "U1") (pin "5") (pinfunction "VIN_5") (pintype "power_in"))
      (node (ref "U1") (pin "6") (pinfunction "EN_6") (pintype "input"))
      (node (ref "U1") (pin "7") (pinfunction "PS_SYNC_7") (pintype "input"))
      (node (ref "U1") (pin "8") (pinfunction "VINA_8") (pintype "power_in"))
      (node (ref "U2") (pin "4") (pinfunction "EN_4") (pintype "input"))
      (node (ref "U2") (pin "5") (pinfunction "IN_5") (pintype "input"))
      (node (ref "V_REF1") (pin "1") (pinfunction "+VS_1") (pintype "input"))
      (node (ref "V_REF2") (pin "1") (pinfunction "+VS_1") (pintype "input"))
      (node (ref "V_REF3") (pin "1") (pinfunction "+VS_1") (pintype "input"))
    )
    (net (code "2") (name "/+X_IN") (class "Default")
      (node (ref "ADC4") (pin "1") (pinfunction "CH0_1") (pintype "bidirectional"))
      (node (ref "U$1") (pin "P$23") (pinfunction "P$23_P$23") (pintype "bidirectional"))
    )
    (net (code "3") (name "/+X_X1") (class "Default")
      (node (ref "C6") (pin "1") (pinfunction "1_1") (pintype "passive"))
      (node (ref "R10") (pin "2") (pinfunction "2_2") (pintype "passive"))
      (node (ref "U$1") (pin "P$34") (pinfunction "P$34_P$34") (pintype "bidirectional"))
      (node (ref "U$31") (pin "P$2") (pinfunction "P$1_P$2") (pintype "bidirectional"))
      (node (ref "U$7") (pin "6") (pinfunction "B_IN-_6") (pintype "bidirectional"))
    )
    (net (code "4") (name "/+X_X2") (class "Default")
      (node (ref "C4") (pin "1") (pinfunction "1_1") (pintype "passive"))
      (node (ref "R6") (pin "2") (pinfunction "2_2") (pintype "passive"))
      (node (ref "U$1") (pin "P$30") (pinfunction "P$30_P$30") (pintype "bidirectional"))
      (node (ref "U$31") (pin "P$4") (pinfunction "P$3_P$4") (pintype "bidirectional"))
      (node (ref "U$6") (pin "6") (pinfunction "B_IN-_6") (pintype "bidirectional"))
    )
    (net (code "5") (name "/+X_Y1") (class "Default")
      (node (ref "C5") (pin "2") (pinfunction "2_2") (pintype "passive"))
      (node (ref "R9") (pin "2") (pinfunction "2_2") (pintype "passive"))
      (node (ref "U$1") (pin "P$32") (pinfunction "P$32_P$32") (pintype "bidirectional"))
      (node (ref "U$31") (pin "P$3") (pinfunction "P$2_P$3") (pintype "bidirectional"))
      (node (ref "U$7") (pin "2") (pinfunction "A_IN-_2") (pintype "bidirectional"))
    )
    (net (code "6") (name "/+X_Y2") (class "Default")
      (node (ref "C3") (pin "2") (pinfunction "2_2") (pintype "passive"))
      (node (ref "R5") (pin "2") (pinfunction "2_2") (pintype "passive"))
      (node (ref "U$1") (pin "P$28") (pinfunction "P$28_P$28") (pintype "bidirectional"))
      (node (ref "U$31") (pin "P$5") (pinfunction "P$4_P$5") (pintype "bidirectional"))
      (node (ref "U$6") (pin "2") (pinfunction "A_IN-_2") (pintype "bidirectional"))
    )
    (net (code "7") (name "/+Z_IN") (class "Default")
      (node (ref "ADC4") (pin "5") (pinfunction "CH4_5") (pintype "bidirectional"))
      (node (ref "U$1") (pin "P$31") (pinfunction "P$31_P$31") (pintype "bidirectional"))
      (node (ref "U$21") (pin "P$10") (pinfunction "P$9_P$10") (pintype "bidirectional"))
    )
    (net (code "8") (name "/+Z_X1") (class "Default")
      (node (ref "C10") (pin "1") (pinfunction "1_1") (pintype "passive"))
      (node (ref "R26") (pin "2") (pinfunction "2_2") (pintype "passive"))
      (node (ref "U$21") (pin "P$5") (pinfunction "P$4_P$5") (pintype "bidirectional"))
      (node (ref "U$9") (pin "6") (pinfunction "B_IN-_6") (pintype "bidirectional"))
    )
    (net (code "9") (name "/+Z_X2") (class "Default")
      (node (ref "C8") (pin "1") (pinfunction "1_1") (pintype "passive"))
      (node (ref "R20") (pin "2") (pinfunction "2_2") (pintype "passive"))
      (node (ref "U$21") (pin "P$7") (pinfunction "P$6_P$7") (pintype "bidirectional"))
      (node (ref "U$8") (pin "6") (pinfunction "B_IN-_6") (pintype "bidirectional"))
    )
    (net (code "10") (name "/+Z_Y1") (class "Default")
      (node (ref "C9") (pin "2") (pinfunction "2_2") (pintype "passive"))
      (node (ref "R25") (pin "2") (pinfunction "2_2") (pintype "passive"))
      (node (ref "U$21") (pin "P$6") (pinfunction "P$5_P$6") (pintype "bidirectional"))
      (node (ref "U$9") (pin "2") (pinfunction "A_IN-_2") (pintype "bidirectional"))
    )
    (net (code "11") (name "/+Z_Y2") (class "Default")
      (node (ref "C7") (pin "2") (pinfunction "2_2") (pintype "passive"))
      (node (ref "R19") (pin "2") (pinfunction "2_2") (pintype "passive"))
      (node (ref "U$21") (pin "P$8") (pinfunction "P$7_P$8") (pintype "bidirectional"))
      (node (ref "U$8") (pin "2") (pinfunction "A_IN-_2") (pintype "bidirectional"))
    )
    (net (code "12") (name "/-X_IN") (class "Default")
      (node (ref "ADC4") (pin "2") (pinfunction "CH1_2") (pintype "bidirectional"))
      (node (ref "U$1") (pin "P$25") (pinfunction "P$25_P$25") (pintype "bidirectional"))
    )
    (net (code "13") (name "/-X_X1") (class "Default")
      (node (ref "C12") (pin "1") (pinfunction "1_1") (pintype "passive"))
      (node (ref "R32") (pin "2") (pinfunction "2_2") (pintype "passive"))
      (node (ref "U$1") (pin "P$51") (pinfunction "P$51_P$51") (pintype "bidirectional"))
      (node (ref "U$10") (pin "6") (pinfunction "B_IN-_6") (pintype "bidirectional"))
      (node (ref "U$32") (pin "P$2") (pinfunction "P$1_P$2") (pintype "bidirectional"))
    )
    (net (code "14") (name "/-X_X2") (class "Default")
      (node (ref "C2") (pin "1") (pinfunction "1_1") (pintype "passive"))
      (node (ref "R2") (pin "2") (pinfunction "2_2") (pintype "passive"))
      (node (ref "U$1") (pin "P$47") (pinfunction "P$47_P$47") (pintype "bidirectional"))
      (node (ref "U$32") (pin "P$4") (pinfunction "P$3_P$4") (pintype "bidirectional"))
      (node (ref "U$5") (pin "6") (pinfunction "B_IN-_6") (pintype "bidirectional"))
    )
    (net (code "15") (name "/-X_Y1") (class "Default")
      (node (ref "C11") (pin "2") (pinfunction "2_2") (pintype "passive"))
      (node (ref "R31") (pin "2") (pinfunction "2_2") (pintype "passive"))
      (node (ref "U$1") (pin "P$49") (pinfunction "P$49_P$49") (pintype "bidirectional"))
      (node (ref "U$10") (pin "2") (pinfunction "A_IN-_2") (pintype "bidirectional"))
      (node (ref "U$32") (pin "P$3") (pinfunction "P$2_P$3") (pintype "bidirectional"))
    )
    (net (code "16") (name "/-X_Y2") (class "Default")
      (node (ref "C1") (pin "2") (pinfunction "2_2") (pintype "passive"))
      (node (ref "R1") (pin "2") (pinfunction "2_2") (pintype "passive"))
      (node (ref "U$1") (pin "P$45") (pinfunction "P$45_P$45") (pintype "bidirectional"))
      (node (ref "U$32") (pin "P$5") (pinfunction "P$4_P$5") (pintype "bidirectional"))
      (node (ref "U$5") (pin "2") (pinfunction "A_IN-_2") (pintype "bidirectional"))
    )
    (net (code "17") (name "/-Y_IN") (class "Default")
      (node (ref "ADC4") (pin "3") (pinfunction "CH2_3") (pintype "bidirectional"))
      (node (ref "U$1") (pin "P$27") (pinfunction "P$27_P$27") (pintype "bidirectional"))
    )
    (net (code "18") (name "/-Y_X1") (class "Default")
      (node (ref "C16") (pin "1") (pinfunction "1_1") (pintype "passive"))
      (node (ref "R44") (pin "2") (pinfunction "2_2") (pintype "passive"))
      (node (ref "U$1") (pin "P$52") (pinfunction "P$52_P$52") (pintype "bidirectional"))
      (node (ref "U$12") (pin "6") (pinfunction "B_IN-_6") (pintype "bidirectional"))
      (node (ref "U$34") (pin "P$2") (pinfunction "P$1_P$2") (pintype "bidirectional"))
    )
    (net (code "19") (name "/-Y_X2") (class "Default")
      (node (ref "C14") (pin "1") (pinfunction "1_1") (pintype "passive"))
      (node (ref "R38") (pin "2") (pinfunction "2_2") (pintype "passive"))
      (node (ref "U$1") (pin "P$48") (pinfunction "P$48_P$48") (pintype "bidirectional"))
      (node (ref "U$11") (pin "6") (pinfunction "B_IN-_6") (pintype "bidirectional"))
      (node (ref "U$34") (pin "P$4") (pinfunction "P$3_P$4") (pintype "bidirectional"))
    )
    (net (code "20") (name "/-Y_Y1") (class "Default")
      (node (ref "C15") (pin "2") (pinfunction "2_2") (pintype "passive"))
      (node (ref "R43") (pin "2") (pinfunction "2_2") (pintype "passive"))
      (node (ref "U$1") (pin "P$50") (pinfunction "P$50_P$50") (pintype "bidirectional"))
      (node (ref "U$12") (pin "2") (pinfunction "A_IN-_2") (pintype "bidirectional"))
      (node (ref "U$34") (pin "P$3") (pinfunction "P$2_P$3") (pintype "bidirectional"))
    )
    (net (code "21") (name "/-Y_Y2") (class "Default")
      (node (ref "C13") (pin "2") (pinfunction "2_2") (pintype "passive"))
      (node (ref "R37") (pin "2") (pinfunction "2_2") (pintype "passive"))
      (node (ref "U$1") (pin "P$46") (pinfunction "P$46_P$46") (pintype "bidirectional"))
      (node (ref "U$11") (pin "2") (pinfunction "A_IN-_2") (pintype "bidirectional"))
      (node (ref "U$34") (pin "P$5") (pinfunction "P$4_P$5") (pintype "bidirectional"))
    )
    (net (code "22") (name "/-Z_IN") (class "Default")
      (node (ref "ADC4") (pin "4") (pinfunction "CH3_4") (pintype "bidirectional"))
      (node (ref "U$1") (pin "P$29") (pinfunction "P$29_P$29") (pintype "bidirectional"))
    )
    (net (code "23") (name "/2.5REF") (class "Default")
      (node (ref "ADC2") (pin "15") (pinfunction "VREF_15") (pintype "power_in"))
      (node (ref "C40") (pin "1") (pinfunction "1_1") (pintype "passive"))
      (node (ref "U$14") (pin "6") (pinfunction "VOUT_6") (pintype "bidirectional"))
      (node (ref "U$14") (pin "7") (pinfunction "VOUT1_7") (pintype "bidirectional"))
    )
    (net (code "24") (name "/3V3_TOLUCA") (class "Default")
      (node (ref "U$1") (pin "P$5") (pinfunction "P$5_P$5") (pintype "bidirectional"))
      (node (ref "U$1") (pin "P$6") (pinfunction "P$6_P$6") (pintype "bidirectional"))
      (node (ref "X_DRV") (pin "4") (pinfunction "VCC_4") (pintype "power_in"))
      (node (ref "X_DRV1") (pin "4") (pinfunction "VCC_4") (pintype "power_in"))
      (node (ref "X_DRV2") (pin "4") (pinfunction "VCC_4") (pintype "power_in"))
    )
    (net (code "25") (name "/3V3_WHISKA") (class "Default")
      (node (ref "R65") (pin "2") (pinfunction "2_2") (pintype "passive"))
      (node (ref "R73") (pin "1") (pinfunction "1_1") (pintype "passive"))
      (node (ref "R74") (pin "2") (pinfunction "2_2") (pintype "passive"))
      (node (ref "U$1") (pin "P$3") (pinfunction "P$3_P$3") (pintype "bidirectional"))
      (node (ref "U$1") (pin "P$4") (pinfunction "P$4_P$4") (pintype "bidirectional"))
      (node (ref "U$15") (pin "P$3") (pinfunction "3_GATEP_P$3") (pintype "bidirectional"))
      (node (ref "U$15") (pin "P$5") (pinfunction "5_IN_P$5") (pintype "bidirectional"))
    )
    (net (code "26") (name "/ADC1_CS") (class "Default")
      (node (ref "ADC1") (pin "10") (pinfunction "CS_10") (pintype "bidirectional"))
      (node (ref "IC1") (pin "39") (pinfunction "PC8_39") (pintype "bidirectional"))
      (node (ref "R50") (pin "2") (pinfunction "2_2") (pintype "passive"))
    )
    (net (code "27") (name "/ADC2_CS") (class "Default")
      (node (ref "ADC3") (pin "10") (pinfunction "CS_10") (pintype "bidirectional"))
      (node (ref "ADC4") (pin "10") (pinfunction "CS_10") (pintype "bidirectional"))
      (node (ref "IC1") (pin "40") (pinfunction "PC9_40") (pintype "bidirectional"))
      (node (ref "R49") (pin "2") (pinfunction "2_2") (pintype "passive"))
      (node (ref "R76") (pin "2") (pinfunction "2_2") (pintype "passive"))
    )
    (net (code "28") (name "/CS_GYRO") (class "Default")
      (node (ref "IC1") (pin "9") (pinfunction "PC1_9") (pintype "bidirectional"))
      (node (ref "R51") (pin "2") (pinfunction "2_2") (pintype "passive"))
      (node (ref "U$4") (pin "CS") (pinfunction "CS_CS") (pintype "bidirectional"))
    )
    (net (code "29") (name "/FAULT_X") (class "Default")
      (node (ref "IC1") (pin "2") (pinfunction "PC13_2") (pintype "bidirectional"))
      (node (ref "X_DRV") (pin "6") (pinfunction "FAULTN_6") (pintype "output"))
    )
    (net (code "30") (name "/FAULT_Y") (class "Default")
      (node (ref "IC1") (pin "3") (pinfunction "PC14_3") (pintype "bidirectional"))
      (node (ref "X_DRV1") (pin "6") (pinfunction "FAULTN_6") (pintype "output"))
    )
    (net (code "31") (name "/FAULT_Z") (class "Default")
      (node (ref "IC1") (pin "4") (pinfunction "PC15_4") (pintype "bidirectional"))
      (node (ref "X_DRV2") (pin "6") (pinfunction "FAULTN_6") (pintype "output"))
    )
    (net (code "32") (name "/FLASH1_CS") (class "Default")
      (node (ref "FLASH_SENSOR") (pin "1") (pinfunction "~{CS}_1") (pintype "input"))
      (node (ref "IC1") (pin "52") (pinfunction "PC11_52") (pintype "bidirectional"))
      (node (ref "R54") (pin "1") (pinfunction "1_1") (pintype "passive"))
    )
    (net (code "33") (name "/FLASH2_CS") (class "Default")
      (node (ref "FLASH_CAM") (pin "1") (pinfunction "~{CS}_1") (pintype "input"))
      (node (ref "IC1") (pin "53") (pinfunction "PC12_53") (pintype "bidirectional"))
      (node (ref "R57") (pin "1") (pinfunction "1_1") (pintype "passive"))
    )
    (net (code "34") (name "/G2") (class "Default")
      (node (ref "U$22") (pin "4") (pinfunction "G2_4") (pintype "power_in"))
    )
    (net (code "35") (name "/GND_SOLAR") (class "Default")
      (node (ref "U$1") (pin "P$57") (pinfunction "P$57_P$57") (pintype "bidirectional"))
      (node (ref "U$1") (pin "P$58") (pinfunction "P$58_P$58") (pintype "bidirectional"))
      (node (ref "U$21") (pin "P$3") (pinfunction "P$2_P$3") (pintype "bidirectional"))
    )
    (net (code "36") (name "/I2C1_SCL") (class "Default")
      (node (ref "IC1") (pin "58") (pinfunction "PB6_58") (pintype "bidirectional"))
      (node (ref "U$3") (pin "5") (pinfunction "SCL_5") (pintype "bidirectional"))
    )
    (net (code "37") (name "/I2C1_SDA") (class "Default")
      (node (ref "IC1") (pin "59") (pinfunction "PB7_59") (pintype "bidirectional"))
      (node (ref "U$3") (pin "6") (pinfunction "SDA_6") (pintype "bidirectional"))
    )
    (net (code "38") (name "/MD_VOL_DEF") (class "Default")
      (node (ref "X_DRV1") (pin "7") (pinfunction "VSET_7") (pintype "input"))
      (node (ref "X_DRV2") (pin "7") (pinfunction "VSET_7") (pintype "input"))
    )
    (net (code "39") (name "/MD_VOL_REF") (class "Default")
      (node (ref "IC1") (pin "20") (pinfunction "PA4_20") (pintype "bidirectional"))
      (node (ref "X_DRV") (pin "7") (pinfunction "VSET_7") (pintype "input"))
    )
    (net (code "40") (name "/NRST_AODS") (class "Default")
      (node (ref "IC1") (pin "7") (pinfunction "NRST_7") (pintype "input"))
      (node (ref "JP1") (pin "5") (pinfunction "5_5") (pintype "passive"))
      (node (ref "U$1") (pin "P$19") (pinfunction "P$19_P$19") (pintype "bidirectional"))
    )
    (net (code "41") (name "/NTC_MAIN_AODS") (class "Default")
      (node (ref "U$1") (pin "P$20") (pinfunction "P$20_P$20") (pintype "bidirectional"))
    )
    (net (code "42") (name "/NTC_SUB_AODS") (class "Default")
      (node (ref "U$1") (pin "P$26") (pinfunction "P$26_P$26") (pintype "bidirectional"))
    )
    (net (code "43") (name "/RESET_AODS") (class "Default")
      (node (ref "R67") (pin "1") (pinfunction "1_1") (pintype "passive"))
      (node (ref "U$1") (pin "P$33") (pinfunction "P$33_P$33") (pintype "bidirectional"))
    )
    (net (code "44") (name "/RX_CAMERA") (class "Default")
      (node (ref "IC1") (pin "43") (pinfunction "PA10_43") (pintype "bidirectional"))
      (node (ref "U$1") (pin "P$56") (pinfunction "P$56_P$56") (pintype "bidirectional"))
    )
    (net (code "45") (name "/RX_MAIN_AODS") (class "Default")
      (node (ref "IC1") (pin "51") (pinfunction "PC10_51") (pintype "bidirectional"))
      (node (ref "U$1") (pin "P$16") (pinfunction "P$16_P$16") (pintype "bidirectional"))
    )
    (net (code "46") (name "/RX_SUB_AODS") (class "Default")
      (node (ref "IC1") (pin "14") (pinfunction "PA0_14") (pintype "bidirectional"))
      (node (ref "U$1") (pin "P$22") (pinfunction "P$22_P$22") (pintype "bidirectional"))
    )
    (net (code "47") (name "/RX_TERMINAL") (class "Default")
      (node (ref "IC1") (pin "17") (pinfunction "PA3_17") (pintype "bidirectional"))
    )
    (net (code "48") (name "/SPI1_MISO") (class "Default")
      (node (ref "ADC1") (pin "12") (pinfunction "MISO_12") (pintype "bidirectional"))
      (node (ref "ADC3") (pin "12") (pinfunction "MISO_12") (pintype "bidirectional"))
      (node (ref "ADC4") (pin "12") (pinfunction "MISO_12") (pintype "bidirectional"))
      (node (ref "FLASH_CAM") (pin "2") (pinfunction "SSO_2") (pintype "output"))
      (node (ref "FLASH_SENSOR") (pin "2") (pinfunction "SSO_2") (pintype "output"))
      (node (ref "IC1") (pin "22") (pinfunction "PA6_22") (pintype "bidirectional"))
      (node (ref "U$4") (pin "SDO") (pinfunction "SDO_SDO") (pintype "bidirectional"))
    )
    (net (code "49") (name "/SPI1_MOSI") (class "Default")
      (node (ref "ADC1") (pin "11") (pinfunction "MOSI_11") (pintype "bidirectional"))
      (node (ref "ADC3") (pin "11") (pinfunction "MOSI_11") (pintype "bidirectional"))
      (node (ref "ADC4") (pin "11") (pinfunction "MOSI_11") (pintype "bidirectional"))
      (node (ref "FLASH_CAM") (pin "5") (pinfunction "SSI_5") (pintype "input"))
      (node (ref "FLASH_SENSOR") (pin "5") (pinfunction "SSI_5") (pintype "input"))
      (node (ref "IC1") (pin "23") (pinfunction "PA7_23") (pintype "bidirectional"))
      (node (ref "U$4") (pin "SDI") (pinfunction "SDI_SDI") (pintype "bidirectional"))
    )
    (net (code "50") (name "/SPI1_SCK") (class "Default")
      (node (ref "ADC1") (pin "13") (pinfunction "SCK_13") (pintype "bidirectional"))
      (node (ref "ADC3") (pin "13") (pinfunction "SCK_13") (pintype "bidirectional"))
      (node (ref "ADC4") (pin "13") (pinfunction "SCK_13") (pintype "bidirectional"))
      (node (ref "FLASH_CAM") (pin "6") (pinfunction "CLK_6") (pintype "input"))
      (node (ref "FLASH_SENSOR") (pin "6") (pinfunction "CLK_6") (pintype "input"))
      (node (ref "IC1") (pin "21") (pinfunction "PA5_21") (pintype "bidirectional"))
      (node (ref "U$4") (pin "SCL") (pinfunction "SCL_SCL") (pintype "bidirectional"))
    )
    (net (code "51") (name "/SWCLK_AODS") (class "Default")
      (node (ref "IC1") (pin "49") (pinfunction "JTCK_49") (pintype "input"))
      (node (ref "JP1") (pin "2") (pinfunction "2_2") (pintype "passive"))
      (node (ref "U$1") (pin "P$15") (pinfunction "P$15_P$15") (pintype "bidirectional"))
    )
    (net (code "52") (name "/SWDIO_AODS") (class "Default")
      (node (ref "IC1") (pin "46") (pinfunction "JTMS_46") (pintype "input"))
      (node (ref "JP1") (pin "4") (pinfunction "4_4") (pintype "passive"))
      (node (ref "U$1") (pin "P$17") (pinfunction "P$17_P$17") (pintype "bidirectional"))
    )
    (net (code "53") (name "/SWO_AODS") (class "Default")
      (node (ref "U$1") (pin "P$21") (pinfunction "P$21_P$21") (pintype "bidirectional"))
    )
    (net (code "54") (name "/THERMAL") (class "Default")
      (node (ref "U$1") (pin "P$14") (pinfunction "P$14_P$14") (pintype "bidirectional"))
      (node (ref "U$21") (pin "P$9") (pinfunction "P$8_P$9") (pintype "bidirectional"))
    )
    (net (code "55") (name "/TOLUCA_X_A") (class "Default")
      (node (ref "U$1") (pin "P$10") (pinfunction "P$10_P$10") (pintype "bidirectional"))
      (node (ref "X_DRV") (pin "3") (pinfunction "OUT1_3") (pintype "output"))
    )
    (net (code "56") (name "/TOLUCA_X_A_IN") (class "Default")
      (node (ref "IC1") (pin "29") (pinfunction "PB10_29") (pintype "bidirectional"))
      (node (ref "X_DRV") (pin "9") (pinfunction "IN1_9") (pintype "bidirectional"))
    )
    (net (code "57") (name "/TOLUCA_X_B") (class "Default")
      (node (ref "U$1") (pin "P$12") (pinfunction "P$12_P$12") (pintype "bidirectional"))
      (node (ref "X_DRV") (pin "1") (pinfunction "OUT2_1") (pintype "output"))
    )
    (net (code "58") (name "/TOLUCA_X_B_IN") (class "Default")
      (node (ref "IC1") (pin "28") (pinfunction "PB2_28") (pintype "bidirectional"))
      (node (ref "X_DRV") (pin "10") (pinfunction "IN2_10") (pintype "input"))
    )
    (net (code "59") (name "/TOLUCA_Y_A") (class "Default")
      (node (ref "U$1") (pin "P$9") (pinfunction "P$9_P$9") (pintype "bidirectional"))
      (node (ref "X_DRV1") (pin "3") (pinfunction "OUT1_3") (pintype "output"))
    )
    (net (code "60") (name "/TOLUCA_Y_A_IN") (class "Default")
      (node (ref "IC1") (pin "37") (pinfunction "PC6_37") (pintype "bidirectional"))
      (node (ref "X_DRV1") (pin "9") (pinfunction "IN1_9") (pintype "bidirectional"))
    )
    (net (code "61") (name "/TOLUCA_Y_B") (class "Default")
      (node (ref "U$1") (pin "P$11") (pinfunction "P$11_P$11") (pintype "bidirectional"))
      (node (ref "X_DRV1") (pin "1") (pinfunction "OUT2_1") (pintype "output"))
    )
    (net (code "62") (name "/TOLUCA_Y_B_IN") (class "Default")
      (node (ref "IC1") (pin "38") (pinfunction "PC7_38") (pintype "bidirectional"))
      (node (ref "X_DRV1") (pin "10") (pinfunction "IN2_10") (pintype "input"))
    )
    (net (code "63") (name "/TOLUCA_Z_A") (class "Default")
      (node (ref "U$1") (pin "P$53") (pinfunction "P$53_P$53") (pintype "bidirectional"))
      (node (ref "X_DRV2") (pin "3") (pinfunction "OUT1_3") (pintype "output"))
    )
    (net (code "64") (name "/TOLUCA_Z_A_IN") (class "Default")
      (node (ref "IC1") (pin "26") (pinfunction "PB0_26") (pintype "bidirectional"))
      (node (ref "X_DRV2") (pin "9") (pinfunction "IN1_9") (pintype "bidirectional"))
    )
    (net (code "65") (name "/TOLUCA_Z_B") (class "Default")
      (node (ref "U$1") (pin "P$55") (pinfunction "P$55_P$55") (pintype "bidirectional"))
      (node (ref "X_DRV2") (pin "1") (pinfunction "OUT2_1") (pintype "output"))
    )
    (net (code "66") (name "/TOLUCA_Z_B_IN") (class "Default")
      (node (ref "IC1") (pin "27") (pinfunction "PB1_27") (pintype "bidirectional"))
      (node (ref "X_DRV2") (pin "10") (pinfunction "IN2_10") (pintype "input"))
    )
    (net (code "67") (name "/TX_CAMERA") (class "Default")
      (node (ref "IC1") (pin "42") (pinfunction "PA9_42") (pintype "bidirectional"))
      (node (ref "U$1") (pin "P$54") (pinfunction "P$54_P$54") (pintype "bidirectional"))
    )
    (net (code "68") (name "/TX_MAIN_AODS") (class "Default")
      (node (ref "IC1") (pin "25") (pinfunction "PC5_25") (pintype "bidirectional"))
      (node (ref "U$1") (pin "P$18") (pinfunction "P$18_P$18") (pintype "bidirectional"))
    )
    (net (code "69") (name "/TX_SUB_AODS") (class "Default")
      (node (ref "IC1") (pin "15") (pinfunction "PA1_15") (pintype "bidirectional"))
      (node (ref "U$1") (pin "P$24") (pinfunction "P$24_P$24") (pintype "bidirectional"))
    )
    (net (code "70") (name "/TX_TERMINAL") (class "Default")
      (node (ref "IC1") (pin "16") (pinfunction "PA2_16") (pintype "bidirectional"))
    )
    (net (code "71") (name "/VCC_STM_AODS") (class "Default")
      (node (ref "C44") (pin "1") (pinfunction "1_1") (pintype "passive"))
      (node (ref "C50") (pin "1") (pinfunction "1_1") (pintype "passive"))
      (node (ref "C51") (pin "1") (pinfunction "1_1") (pintype "passive"))
      (node (ref "C52") (pin "1") (pinfunction "1_1") (pintype "passive"))
      (node (ref "C53") (pin "1") (pinfunction "1_1") (pintype "passive"))
      (node (ref "C60") (pin "1") (pinfunction "1_1") (pintype "passive"))
      (node (ref "C62") (pin "1") (pinfunction "1_1") (pintype "passive"))
      (node (ref "IC1") (pin "1") (pinfunction "VBAT_1") (pintype "passive"))
      (node (ref "IC1") (pin "13") (pinfunction "VDDA_13") (pintype "power_in"))
      (node (ref "IC1") (pin "19") (pinfunction "VDD_19") (pintype "power_in"))
      (node (ref "IC1") (pin "32") (pinfunction "VDD_32") (pintype "power_in"))
      (node (ref "IC1") (pin "48") (pinfunction "VDD_48") (pintype "power_in"))
      (node (ref "IC1") (pin "64") (pinfunction "VDD_64") (pintype "power_in"))
      (node (ref "JP1") (pin "1") (pinfunction "1_1") (pintype "passive"))
      (node (ref "R80") (pin "1") (pinfunction "1_1") (pintype "passive"))
      (node (ref "U$1") (pin "P$13") (pinfunction "P$13_P$13") (pintype "bidirectional"))
      (node (ref "U$17") (pin "P$2") (pinfunction "2_OUT_P$2") (pintype "bidirectional"))
      (node (ref "U$19") (pin "1") (pinfunction "S1_1") (pintype "input"))
    )
    (net (code "72") (name "/WHISKA_CS") (class "Default")
      (node (ref "U$1") (pin "P$42") (pinfunction "P$42_P$42") (pintype "bidirectional"))
    )
    (net (code "73") (name "/WHISKA_SPI_CLK") (class "Default")
      (node (ref "ADC2") (pin "13") (pinfunction "SCK_13") (pintype "bidirectional"))
      (node (ref "U$1") (pin "P$40") (pinfunction "P$40_P$40") (pintype "bidirectional"))
    )
    (net (code "74") (name "/WHISKA_SPI_CS") (class "Default")
      (node (ref "ADC2") (pin "10") (pinfunction "CS_10") (pintype "bidirectional"))
      (node (ref "R58") (pin "1") (pinfunction "1_1") (pintype "passive"))
    )
    (net (code "75") (name "/WHISKA_SPI_IN") (class "Default")
      (node (ref "ADC2") (pin "12") (pinfunction "MISO_12") (pintype "bidirectional"))
      (node (ref "U$1") (pin "P$38") (pinfunction "P$38_P$38") (pintype "bidirectional"))
    )
    (net (code "76") (name "/WHISKA_SPI_OUT") (class "Default")
      (node (ref "ADC2") (pin "11") (pinfunction "MOSI_11") (pintype "bidirectional"))
      (node (ref "U$1") (pin "P$36") (pinfunction "P$36_P$36") (pintype "bidirectional"))
    )
    (net (code "77") (name "/WHISKA_SW") (class "Default")
      (node (ref "U$1") (pin "P$44") (pinfunction "P$44_P$44") (pintype "bidirectional"))
      (node (ref "U$22") (pin "2") (pinfunction "G1_2") (pintype "output"))
    )
    (net (code "78") (name "GND") (class "Default")
      (node (ref "ADC1") (pin "14") (pinfunction "AGND_14") (pintype "power_in"))
      (node (ref "ADC1") (pin "9") (pinfunction "GND_9") (pintype "power_in"))
      (node (ref "ADC2") (pin "14") (pinfunction "AGND_14") (pintype "power_in"))
      (node (ref "ADC2") (pin "9") (pinfunction "GND_9") (pintype "power_in"))
      (node (ref "ADC3") (pin "14") (pinfunction "AGND_14") (pintype "power_in"))
      (node (ref "ADC3") (pin "9") (pinfunction "GND_9") (pintype "power_in"))
      (node (ref "ADC4") (pin "14") (pinfunction "AGND_14") (pintype "power_in"))
      (node (ref "ADC4") (pin "9") (pinfunction "GND_9") (pintype "power_in"))
      (node (ref "C17") (pin "2") (pinfunction "2_2") (pintype "passive"))
      (node (ref "C18") (pin "2") (pinfunction "2_2") (pintype "passive"))
      (node (ref "C19") (pin "2") (pinfunction "2_2") (pintype "passive"))
      (node (ref "C20") (pin "2") (pinfunction "2_2") (pintype "passive"))
      (node (ref "C21") (pin "2") (pinfunction "2_2") (pintype "passive"))
      (node (ref "C22") (pin "2") (pinfunction "2_2") (pintype "passive"))
      (node (ref "C23") (pin "2") (pinfunction "2_2") (pintype "passive"))
      (node (ref "C24") (pin "2") (pinfunction "2_2") (pintype "passive"))
      (node (ref "C25") (pin "2") (pinfunction "2_2") (pintype "passive"))
      (node (ref "C26") (pin "2") (pinfunction "2_2") (pintype "passive"))
      (node (ref "C27") (pin "2") (pinfunction "2_2") (pintype "passive"))
      (node (ref "C28") (pin "2") (pinfunction "2_2") (pintype "passive"))
      (node (ref "C29") (pin "2") (pinfunction "2_2") (pintype "passive"))
      (node (ref "C30") (pin "2") (pinfunction "2_2") (pintype "passive"))
      (node (ref "C31") (pin "2") (pinfunction "2_2") (pintype "passive"))
      (node (ref "C32") (pin "2") (pinfunction "2_2") (pintype "passive"))
      (node (ref "C33") (pin "2") (pinfunction "2_2") (pintype "passive"))
      (node (ref "C34") (pin "2") (pinfunction "2_2") (pintype "passive"))
      (node (ref "C35") (pin "2") (pinfunction "2_2") (pintype "passive"))
      (node (ref "C36") (pin "2") (pinfunction "2_2") (pintype "passive"))
      (node (ref "C37") (pin "2") (pinfunction "2_2") (pintype "passive"))
      (node (ref "C38") (pin "2") (pinfunction "2_2") (pintype "passive"))
      (node (ref "C39") (pin "2") (pinfunction "2_2") (pintype "passive"))
      (node (ref "C40") (pin "2") (pinfunction "2_2") (pintype "passive"))
      (node (ref "C41") (pin "2") (pinfunction "2_2") (pintype "passive"))
      (node (ref "C42") (pin "2") (pinfunction "2_2") (pintype "passive"))
      (node (ref "C43") (pin "2") (pinfunction "2_2") (pintype "passive"))
      (node (ref "C44") (pin "2") (pinfunction "2_2") (pintype "passive"))
      (node (ref "C45") (pin "2") (pinfunction "2_2") (pintype "passive"))
      (node (ref "C46") (pin "2") (pinfunction "2_2") (pintype "passive"))
      (node (ref "C47") (pin "2") (pinfunction "2_2") (pintype "passive"))
      (node (ref "C48") (pin "2") (pinfunction "2_2") (pintype "passive"))
      (node (ref "C49") (pin "2") (pinfunction "2_2") (pintype "passive"))
      (node (ref "C50") (pin "2") (pinfunction "2_2") (pintype "passive"))
      (node (ref "C51") (pin "2") (pinfunction "2_2") (pintype "passive"))
      (node (ref "C52") (pin "2") (pinfunction "2_2") (pintype "passive"))
      (node (ref "C53") (pin "2") (pinfunction "2_2") (pintype "passive"))
      (node (ref "C54") (pin "2") (pinfunction "2_2") (pintype "passive"))
      (node (ref "C55") (pin "2") (pinfunction "2_2") (pintype "passive"))
      (node (ref "C56") (pin "2") (pinfunction "2_2") (pintype "passive"))
      (node (ref "C57") (pin "2") (pinfunction "2_2") (pintype "passive"))
      (node (ref "C58") (pin "2") (pinfunction "2_2") (pintype "passive"))
      (node (ref "C59") (pin "2") (pinfunction "2_2") (pintype "passive"))
      (node (ref "C60") (pin "2") (pinfunction "2_2") (pintype "passive"))
      (node (ref "C61") (pin "2") (pinfunction "2_2") (pintype "passive"))
      (node (ref "C62") (pin "2") (pinfunction "2_2") (pintype "passive"))
      (node (ref "FLASH_CAM") (pin "4") (pinfunction "VSS_4") (pintype "power_in"))
      (node (ref "FLASH_SENSOR") (pin "4") (pinfunction "VSS_4") (pintype "power_in"))
      (node (ref "IC1") (pin "12") (pinfunction "VSSA_12") (pintype "power_in"))
      (node (ref "IC1") (pin "18") (pinfunction "VSS_18") (pintype "power_in"))
      (node (ref "IC1") (pin "31") (pinfunction "VSS_31") (pintype "power_in"))
      (node (ref "IC1") (pin "47") (pinfunction "VSS_47") (pintype "power_in"))
      (node (ref "IC1") (pin "60") (pinfunction "BOOT0_60") (pintype "input"))
      (node (ref "IC1") (pin "63") (pinfunction "VSS_63") (pintype "power_in"))
      (node (ref "JP1") (pin "3") (pinfunction "3_3") (pintype "passive"))
      (node (ref "Q1") (pin "2") (pinfunction "S_2") (pintype "passive"))
      (node (ref "Q3") (pin "2") (pinfunction "S_2") (pintype "passive"))
      (node (ref "R59") (pin "2") (pinfunction "2_2") (pintype "passive"))
      (node (ref "R64") (pin "2") (pinfunction "2_2") (pintype "passive"))
      (node (ref "R70") (pin "2") (pinfunction "2_2") (pintype "passive"))
      (node (ref "R71") (pin "1") (pinfunction "1_1") (pintype "passive"))
      (node (ref "R75") (pin "1") (pinfunction "1_1") (pintype "passive"))
      (node (ref "R79") (pin "1") (pinfunction "1_1") (pintype "passive"))
      (node (ref "R84") (pin "2") (pinfunction "2_2") (pintype "passive"))
      (node (ref "R85") (pin "1") (pinfunction "1_1") (pintype "passive"))
      (node (ref "R86") (pin "1") (pinfunction "1_1") (pintype "passive"))
      (node (ref "R87") (pin "2") (pinfunction "2_2") (pintype "passive"))
      (node (ref "R88") (pin "2") (pinfunction "2_2") (pintype "passive"))
      (node (ref "R89") (pin "1") (pinfunction "1_1") (pintype "passive"))
      (node (ref "R90") (pin "2") (pinfunction "2_2") (pintype "passive"))
      (node (ref "R92") (pin "1") (pinfunction "1_1") (pintype "passive"))
      (node (ref "U$1") (pin "P$59") (pinfunction "P$59_P$59") (pintype "bidirectional"))
      (node (ref "U$1") (pin "P$60") (pinfunction "P$60_P$60") (pintype "bidirectional"))
      (node (ref "U$10") (pin "10") (pinfunction "C_IN+_10") (pintype "bidirectional"))
      (node (ref "U$10") (pin "12") (pinfunction "D_IN+_12") (pintype "bidirectional"))
      (node (ref "U$10") (pin "3") (pinfunction "A_IN+_3") (pintype "bidirectional"))
      (node (ref "U$10") (pin "5") (pinfunction "B_IN+_5") (pintype "bidirectional"))
      (node (ref "U$11") (pin "10") (pinfunction "C_IN+_10") (pintype "bidirectional"))
      (node (ref "U$11") (pin "12") (pinfunction "D_IN+_12") (pintype "bidirectional"))
      (node (ref "U$11") (pin "3") (pinfunction "A_IN+_3") (pintype "bidirectional"))
      (node (ref "U$11") (pin "5") (pinfunction "B_IN+_5") (pintype "bidirectional"))
      (node (ref "U$12") (pin "10") (pinfunction "C_IN+_10") (pintype "bidirectional"))
      (node (ref "U$12") (pin "12") (pinfunction "D_IN+_12") (pintype "bidirectional"))
      (node (ref "U$12") (pin "3") (pinfunction "A_IN+_3") (pintype "bidirectional"))
      (node (ref "U$12") (pin "5") (pinfunction "B_IN+_5") (pintype "bidirectional"))
      (node (ref "U$13") (pin "3") (pinfunction "3_3") (pintype "passive"))
      (node (ref "U$14") (pin "2") (pinfunction "GND_2") (pintype "bidirectional"))
      (node (ref "U$14") (pin "3") (pinfunction "GND1_3") (pintype "bidirectional"))
      (node (ref "U$15") (pin "P$4") (pinfunction "4_GND_P$4") (pintype "bidirectional"))
      (node (ref "U$16") (pin "3") (pinfunction "S2_3") (pintype "input"))
      (node (ref "U$17") (pin "P$4") (pinfunction "4_GND_P$4") (pintype "bidirectional"))
      (node (ref "U$18") (pin "P$2") (pinfunction "2V-_P$2") (pintype "bidirectional"))
      (node (ref "U$19") (pin "3") (pinfunction "S2_3") (pintype "input"))
      (node (ref "U$21") (pin "P$2") (pinfunction "P$1_P$2") (pintype "bidirectional"))
      (node (ref "U$26") (pin "1") (pinfunction "1_1") (pintype "passive"))
      (node (ref "U$3") (pin "1") (pinfunction "GND_1") (pintype "bidirectional"))
      (node (ref "U$4") (pin "GND") (pinfunction "GND_GND") (pintype "bidirectional"))
      (node (ref "U$5") (pin "10") (pinfunction "C_IN+_10") (pintype "bidirectional"))
      (node (ref "U$5") (pin "12") (pinfunction "D_IN+_12") (pintype "bidirectional"))
      (node (ref "U$5") (pin "3") (pinfunction "A_IN+_3") (pintype "bidirectional"))
      (node (ref "U$5") (pin "5") (pinfunction "B_IN+_5") (pintype "bidirectional"))
      (node (ref "U$6") (pin "10") (pinfunction "C_IN+_10") (pintype "bidirectional"))
      (node (ref "U$6") (pin "12") (pinfunction "D_IN+_12") (pintype "bidirectional"))
      (node (ref "U$6") (pin "3") (pinfunction "A_IN+_3") (pintype "bidirectional"))
      (node (ref "U$6") (pin "5") (pinfunction "B_IN+_5") (pintype "bidirectional"))
      (node (ref "U$7") (pin "10") (pinfunction "C_IN+_10") (pintype "bidirectional"))
      (node (ref "U$7") (pin "12") (pinfunction "D_IN+_12") (pintype "bidirectional"))
      (node (ref "U$7") (pin "3") (pinfunction "A_IN+_3") (pintype "bidirectional"))
      (node (ref "U$7") (pin "5") (pinfunction "B_IN+_5") (pintype "bidirectional"))
      (node (ref "U$8") (pin "10") (pinfunction "C_IN+_10") (pintype "bidirectional"))
      (node (ref "U$8") (pin "12") (pinfunction "D_IN+_12") (pintype "bidirectional"))
      (node (ref "U$8") (pin "3") (pinfunction "A_IN+_3") (pintype "bidirectional"))
      (node (ref "U$8") (pin "5") (pinfunction "B_IN+_5") (pintype "bidirectional"))
      (node (ref "U$9") (pin "10") (pinfunction "C_IN+_10") (pintype "bidirectional"))
      (node (ref "U$9") (pin "12") (pinfunction "D_IN+_12") (pintype "bidirectional"))
      (node (ref "U$9") (pin "3") (pinfunction "A_IN+_3") (pintype "bidirectional"))
      (node (ref "U$9") (pin "5") (pinfunction "B_IN+_5") (pintype "bidirectional"))
      (node (ref "U1") (pin "11") (pinfunction "PAD_11") (pintype "power_in"))
      (node (ref "U1") (pin "3") (pinfunction "PGND_3") (pintype "power_in"))
      (node (ref "U1") (pin "9") (pinfunction "GND_9") (pintype "power_in"))
      (node (ref "U1") (pin "P$1") (pinfunction "PAD_P$1") (pintype "power_in"))
      (node (ref "U1") (pin "P$2") (pinfunction "PAD_P$2") (pintype "power_in"))
      (node (ref "U1") (pin "P$3") (pinfunction "PAD_P$3") (pintype "power_in"))
      (node (ref "U1") (pin "P$4") (pinfunction "PAD_P$4") (pintype "power_in"))
      (node (ref "U1") (pin "V") (pinfunction "PAD_V") (pintype "power_in"))
      (node (ref "U2") (pin "11") (pinfunction "GND_11") (pintype "power_in"))
      (node (ref "U2") (pin "12") (pinfunction "GND_12") (pintype "power_in"))
      (node (ref "U2") (pin "13") (pinfunction "GND_13") (pintype "power_in"))
      (node (ref "U2") (pin "14") (pinfunction "GND_14") (pintype "power_in"))
      (node (ref "U2") (pin "15") (pinfunction "GND_15") (pintype "power_in"))
      (node (ref "U2") (pin "2") (pinfunction "GND_2") (pintype "power_in"))
      (node (ref "U2") (pin "7") (pinfunction "PS_GND_7") (pintype "input"))
      (node (ref "V_REF1") (pin "3") (pinfunction "GND_3") (pintype "power_in"))
      (node (ref "V_REF2") (pin "3") (pinfunction "GND_3") (pintype "power_in"))
      (node (ref "V_REF3") (pin "3") (pinfunction "GND_3") (pintype "power_in"))
      (node (ref "X_DRV") (pin "11") (pinfunction "EPAD_11") (pintype "passive"))
      (node (ref "X_DRV") (pin "5") (pinfunction "GND_5") (pintype "power_in"))
      (node (ref "X_DRV1") (pin "11") (pinfunction "EPAD_11") (pintype "passive"))
      (node (ref "X_DRV1") (pin "5") (pinfunction "GND_5") (pintype "power_in"))
      (node (ref "X_DRV2") (pin "11") (pinfunction "EPAD_11") (pintype "passive"))
      (node (ref "X_DRV2") (pin "5") (pinfunction "GND_5") (pintype "power_in"))
    )
    (net (code "79") (name "Net-(ADC1-CH0)") (class "Default")
      (node (ref "ADC1") (pin "1") (pinfunction "CH0_1") (pintype "bidirectional"))
      (node (ref "R15") (pin "2") (pinfunction "2_2") (pintype "passive"))
      (node (ref "U$6") (pin "14") (pinfunction "D_OUT_14") (pintype "bidirectional"))
    )
    (net (code "80") (name "Net-(ADC1-CH1)") (class "Default")
      (node (ref "ADC1") (pin "2") (pinfunction "CH1_2") (pintype "bidirectional"))
      (node (ref "R16") (pin "1") (pinfunction "1_1") (pintype "passive"))
      (node (ref "U$6") (pin "8") (pinfunction "C_OUT_8") (pintype "bidirectional"))
    )
    (net (code "81") (name "Net-(ADC1-CH2)") (class "Default")
      (node (ref "ADC1") (pin "3") (pinfunction "CH2_3") (pintype "bidirectional"))
      (node (ref "R17") (pin "2") (pinfunction "2_2") (pintype "passive"))
      (node (ref "U$7") (pin "14") (pinfunction "D_OUT_14") (pintype "bidirectional"))
    )
    (net (code "82") (name "Net-(ADC1-CH3)") (class "Default")
      (node (ref "ADC1") (pin "4") (pinfunction "CH3_4") (pintype "bidirectional"))
      (node (ref "R18") (pin "1") (pinfunction "1_1") (pintype "passive"))
      (node (ref "U$7") (pin "8") (pinfunction "C_OUT_8") (pintype "bidirectional"))
    )
    (net (code "83") (name "Net-(ADC1-CH4)") (class "Default")
      (node (ref "ADC1") (pin "5") (pinfunction "CH4_5") (pintype "bidirectional"))
      (node (ref "R13") (pin "2") (pinfunction "2_2") (pintype "passive"))
      (node (ref "U$5") (pin "14") (pinfunction "D_OUT_14") (pintype "bidirectional"))
    )
    (net (code "84") (name "Net-(ADC1-CH5)") (class "Default")
      (node (ref "ADC1") (pin "6") (pinfunction "CH5_6") (pintype "bidirectional"))
      (node (ref "R14") (pin "1") (pinfunction "1_1") (pintype "passive"))
      (node (ref "U$5") (pin "8") (pinfunction "C_OUT_8") (pintype "bidirectional"))
    )
    (net (code "85") (name "Net-(ADC1-CH6)") (class "Default")
      (node (ref "ADC1") (pin "7") (pinfunction "CH6_7") (pintype "bidirectional"))
      (node (ref "R35") (pin "2") (pinfunction "2_2") (pintype "passive"))
      (node (ref "U$10") (pin "14") (pinfunction "D_OUT_14") (pintype "bidirectional"))
    )
    (net (code "86") (name "Net-(ADC1-CH7)") (class "Default")
      (node (ref "ADC1") (pin "8") (pinfunction "CH7_8") (pintype "bidirectional"))
      (node (ref "R36") (pin "1") (pinfunction "1_1") (pintype "passive"))
      (node (ref "U$10") (pin "8") (pinfunction "C_OUT_8") (pintype "bidirectional"))
    )
    (net (code "87") (name "Net-(ADC1-VREF)") (class "Default")
      (node (ref "ADC1") (pin "15") (pinfunction "VREF_15") (pintype "power_in"))
      (node (ref "C23") (pin "1") (pinfunction "1_1") (pintype "passive"))
      (node (ref "V_REF1") (pin "2") (pinfunction "VO_2") (pintype "input"))
    )
    (net (code "88") (name "Net-(ADC2-CH2)") (class "Default")
      (node (ref "ADC2") (pin "3") (pinfunction "CH2_3") (pintype "bidirectional"))
      (node (ref "R70") (pin "1") (pinfunction "1_1") (pintype "passive"))
      (node (ref "U$18") (pin "P$1") (pinfunction "1OUT_P$1") (pintype "bidirectional"))
    )
    (net (code "89") (name "Net-(ADC2-CH3)") (class "Default")
      (node (ref "ADC2") (pin "4") (pinfunction "CH3_4") (pintype "bidirectional"))
      (node (ref "R90") (pin "1") (pinfunction "1_1") (pintype "passive"))
      (node (ref "U$27") (pin "P$8") (pinfunction "8_PWRGD_P$8") (pintype "bidirectional"))
    )
    (net (code "90") (name "Net-(ADC2-CH4)") (class "Default")
      (node (ref "ADC2") (pin "5") (pinfunction "CH4_5") (pintype "bidirectional"))
      (node (ref "R88") (pin "1") (pinfunction "1_1") (pintype "passive"))
      (node (ref "U$27") (pin "P$6") (pinfunction "6_SENSE_P$6") (pintype "bidirectional"))
    )
    (net (code "91") (name "Net-(ADC2-CH5)") (class "Default")
      (node (ref "ADC2") (pin "6") (pinfunction "CH5_6") (pintype "bidirectional"))
      (node (ref "R87") (pin "1") (pinfunction "1_1") (pintype "passive"))
      (node (ref "WHISKAPAD1") (pin "P$1") (pinfunction "P$1_P$1") (pintype "bidirectional"))
    )
    (net (code "92") (name "Net-(ADC2-CH6)") (class "Default")
      (node (ref "ADC2") (pin "7") (pinfunction "CH6_7") (pintype "bidirectional"))
      (node (ref "R84") (pin "1") (pinfunction "1_1") (pintype "passive"))
      (node (ref "U$23") (pin "P$6") (pinfunction "6_SENSE_P$6") (pintype "bidirectional"))
    )
    (net (code "93") (name "Net-(ADC2-CH7)") (class "Default")
      (node (ref "ADC2") (pin "8") (pinfunction "CH7_8") (pintype "bidirectional"))
      (node (ref "R64") (pin "1") (pinfunction "1_1") (pintype "passive"))
      (node (ref "WHISKAPAD2") (pin "P$1") (pinfunction "P$1_P$1") (pintype "bidirectional"))
    )
    (net (code "94") (name "Net-(ADC3-CH0)") (class "Default")
      (node (ref "ADC3") (pin "1") (pinfunction "CH0_1") (pintype "bidirectional"))
      (node (ref "R23") (pin "2") (pinfunction "2_2") (pintype "passive"))
      (node (ref "U$8") (pin "14") (pinfunction "D_OUT_14") (pintype "bidirectional"))
    )
    (net (code "95") (name "Net-(ADC3-CH1)") (class "Default")
      (node (ref "ADC3") (pin "2") (pinfunction "CH1_2") (pintype "bidirectional"))
      (node (ref "R24") (pin "1") (pinfunction "1_1") (pintype "passive"))
      (node (ref "U$8") (pin "8") (pinfunction "C_OUT_8") (pintype "bidirectional"))
    )
    (net (code "96") (name "Net-(ADC3-CH2)") (class "Default")
      (node (ref "ADC3") (pin "3") (pinfunction "CH2_3") (pintype "bidirectional"))
      (node (ref "R29") (pin "2") (pinfunction "2_2") (pintype "passive"))
      (node (ref "U$9") (pin "14") (pinfunction "D_OUT_14") (pintype "bidirectional"))
    )
    (net (code "97") (name "Net-(ADC3-CH3)") (class "Default")
      (node (ref "ADC3") (pin "4") (pinfunction "CH3_4") (pintype "bidirectional"))
      (node (ref "R30") (pin "1") (pinfunction "1_1") (pintype "passive"))
      (node (ref "U$9") (pin "8") (pinfunction "C_OUT_8") (pintype "bidirectional"))
    )
    (net (code "98") (name "Net-(ADC3-CH4)") (class "Default")
      (node (ref "ADC3") (pin "5") (pinfunction "CH4_5") (pintype "bidirectional"))
      (node (ref "R41") (pin "2") (pinfunction "2_2") (pintype "passive"))
      (node (ref "U$11") (pin "14") (pinfunction "D_OUT_14") (pintype "bidirectional"))
    )
    (net (code "99") (name "Net-(ADC3-CH5)") (class "Default")
      (node (ref "ADC3") (pin "6") (pinfunction "CH5_6") (pintype "bidirectional"))
      (node (ref "R42") (pin "1") (pinfunction "1_1") (pintype "passive"))
      (node (ref "U$11") (pin "8") (pinfunction "C_OUT_8") (pintype "bidirectional"))
    )
    (net (code "100") (name "Net-(ADC3-CH6)") (class "Default")
      (node (ref "ADC3") (pin "7") (pinfunction "CH6_7") (pintype "bidirectional"))
      (node (ref "R47") (pin "2") (pinfunction "2_2") (pintype "passive"))
      (node (ref "U$12") (pin "14") (pinfunction "D_OUT_14") (pintype "bidirectional"))
    )
    (net (code "101") (name "Net-(ADC3-CH7)") (class "Default")
      (node (ref "ADC3") (pin "8") (pinfunction "CH7_8") (pintype "bidirectional"))
      (node (ref "R48") (pin "1") (pinfunction "1_1") (pintype "passive"))
      (node (ref "U$12") (pin "8") (pinfunction "C_OUT_8") (pintype "bidirectional"))
    )
    (net (code "102") (name "Net-(ADC3-VREF)") (class "Default")
      (node (ref "ADC3") (pin "15") (pinfunction "VREF_15") (pintype "power_in"))
      (node (ref "C27") (pin "1") (pinfunction "1_1") (pintype "passive"))
      (node (ref "V_REF2") (pin "2") (pinfunction "VO_2") (pintype "input"))
    )
    (net (code "103") (name "Net-(ADC4-VREF)") (class "Default")
      (node (ref "ADC4") (pin "15") (pinfunction "VREF_15") (pintype "power_in"))
      (node (ref "C48") (pin "1") (pinfunction "1_1") (pintype "passive"))
      (node (ref "V_REF3") (pin "2") (pinfunction "VO_2") (pintype "input"))
    )
    (net (code "104") (name "Net-(FLASH_CAM-~{HOLD})") (class "Default")
      (node (ref "FLASH_CAM") (pin "7") (pinfunction "~{HOLD}_7") (pintype "input"))
      (node (ref "R55") (pin "1") (pinfunction "1_1") (pintype "passive"))
    )
    (net (code "105") (name "Net-(FLASH_CAM-~{W})") (class "Default")
      (node (ref "FLASH_CAM") (pin "3") (pinfunction "~{W}_3") (pintype "input"))
      (node (ref "R56") (pin "1") (pinfunction "1_1") (pintype "passive"))
    )
    (net (code "106") (name "Net-(FLASH_SENSOR-~{HOLD})") (class "Default")
      (node (ref "FLASH_SENSOR") (pin "7") (pinfunction "~{HOLD}_7") (pintype "input"))
      (node (ref "R52") (pin "1") (pinfunction "1_1") (pintype "passive"))
    )
    (net (code "107") (name "Net-(FLASH_SENSOR-~{W})") (class "Default")
      (node (ref "FLASH_SENSOR") (pin "3") (pinfunction "~{W}_3") (pintype "input"))
      (node (ref "R53") (pin "1") (pinfunction "1_1") (pintype "passive"))
    )
    (net (code "108") (name "Net-(IC1-VCAP1)") (class "Default")
      (node (ref "C61") (pin "1") (pinfunction "1_1") (pintype "passive"))
      (node (ref "IC1") (pin "30") (pinfunction "VCAP1_30") (pintype "passive"))
    )
    (net (code "109") (name "Net-(Q1-D)") (class "Default")
      (node (ref "Q1") (pin "3") (pinfunction "D_3") (pintype "passive"))
      (node (ref "R81") (pin "2") (pinfunction "2_2") (pintype "passive"))
      (node (ref "U$19") (pin "4") (pinfunction "G2_4") (pintype "power_in"))
    )
    (net (code "110") (name "Net-(Q1-G)") (class "Default")
      (node (ref "Q1") (pin "1") (pinfunction "G_1") (pintype "passive"))
      (node (ref "U$17") (pin "P$7") (pinfunction "7_GATE_P$7") (pintype "bidirectional"))
      (node (ref "U$19") (pin "2") (pinfunction "G1_2") (pintype "output"))
    )
    (net (code "111") (name "Net-(Q3-D)") (class "Default")
      (node (ref "Q3") (pin "3") (pinfunction "D_3") (pintype "passive"))
      (node (ref "R73") (pin "2") (pinfunction "2_2") (pintype "passive"))
      (node (ref "U$16") (pin "4") (pinfunction "G2_4") (pintype "power_in"))
    )
    (net (code "112") (name "Net-(Q3-G)") (class "Default")
      (node (ref "Q3") (pin "1") (pinfunction "G_1") (pintype "passive"))
      (node (ref "U$15") (pin "P$7") (pinfunction "7_GATE_P$7") (pintype "bidirectional"))
      (node (ref "U$16") (pin "2") (pinfunction "G1_2") (pintype "output"))
    )
    (net (code "113") (name "Net-(R67-Pad2)") (class "Default")
      (node (ref "R67") (pin "2") (pinfunction "2_2") (pintype "passive"))
      (node (ref "R75") (pin "2") (pinfunction "2_2") (pintype "passive"))
      (node (ref "U$20") (pin "B") (pinfunction "B_B") (pintype "bidirectional"))
    )
    (net (code "114") (name "Net-(U$5-A_OUT)") (class "Default")
      (node (ref "C1") (pin "1") (pinfunction "1_1") (pintype "passive"))
      (node (ref "R1") (pin "1") (pinfunction "1_1") (pintype "passive"))
      (node (ref "R3") (pin "1") (pinfunction "1_1") (pintype "passive"))
      (node (ref "U$5") (pin "1") (pinfunction "A_OUT_1") (pintype "bidirectional"))
    )
    (net (code "115") (name "Net-(U$5-B_OUT)") (class "Default")
      (node (ref "C2") (pin "2") (pinfunction "2_2") (pintype "passive"))
      (node (ref "R2") (pin "1") (pinfunction "1_1") (pintype "passive"))
      (node (ref "R4") (pin "1") (pinfunction "1_1") (pintype "passive"))
      (node (ref "U$5") (pin "7") (pinfunction "B_OUT_7") (pintype "bidirectional"))
    )
    (net (code "116") (name "Net-(U$5-C_IN-)") (class "Default")
      (node (ref "R14") (pin "2") (pinfunction "2_2") (pintype "passive"))
      (node (ref "R4") (pin "2") (pinfunction "2_2") (pintype "passive"))
      (node (ref "U$5") (pin "9") (pinfunction "C_IN-_9") (pintype "bidirectional"))
    )
    (net (code "117") (name "Net-(U$5-D_IN-)") (class "Default")
      (node (ref "R13") (pin "1") (pinfunction "1_1") (pintype "passive"))
      (node (ref "R3") (pin "2") (pinfunction "2_2") (pintype "passive"))
      (node (ref "U$5") (pin "13") (pinfunction "D_IN-_13") (pintype "bidirectional"))
    )
    (net (code "118") (name "Net-(U$6-A_OUT)") (class "Default")
      (node (ref "C3") (pin "1") (pinfunction "1_1") (pintype "passive"))
      (node (ref "R5") (pin "1") (pinfunction "1_1") (pintype "passive"))
      (node (ref "R7") (pin "1") (pinfunction "1_1") (pintype "passive"))
      (node (ref "U$6") (pin "1") (pinfunction "A_OUT_1") (pintype "bidirectional"))
    )
    (net (code "119") (name "Net-(U$6-B_OUT)") (class "Default")
      (node (ref "C4") (pin "2") (pinfunction "2_2") (pintype "passive"))
      (node (ref "R6") (pin "1") (pinfunction "1_1") (pintype "passive"))
      (node (ref "R8") (pin "1") (pinfunction "1_1") (pintype "passive"))
      (node (ref "U$6") (pin "7") (pinfunction "B_OUT_7") (pintype "bidirectional"))
    )
    (net (code "120") (name "Net-(U$6-C_IN-)") (class "Default")
      (node (ref "R16") (pin "2") (pinfunction "2_2") (pintype "passive"))
      (node (ref "R8") (pin "2") (pinfunction "2_2") (pintype "passive"))
      (node (ref "U$6") (pin "9") (pinfunction "C_IN-_9") (pintype "bidirectional"))
    )
    (net (code "121") (name "Net-(U$6-D_IN-)") (class "Default")
      (node (ref "R15") (pin "1") (pinfunction "1_1") (pintype "passive"))
      (node (ref "R7") (pin "2") (pinfunction "2_2") (pintype "passive"))
      (node (ref "U$6") (pin "13") (pinfunction "D_IN-_13") (pintype "bidirectional"))
    )
    (net (code "122") (name "Net-(U$7-A_OUT)") (class "Default")
      (node (ref "C5") (pin "1") (pinfunction "1_1") (pintype "passive"))
      (node (ref "R11") (pin "1") (pinfunction "1_1") (pintype "passive"))
      (node (ref "R9") (pin "1") (pinfunction "1_1") (pintype "passive"))
      (node (ref "U$7") (pin "1") (pinfunction "A_OUT_1") (pintype "bidirectional"))
    )
    (net (code "123") (name "Net-(U$7-B_OUT)") (class "Default")
      (node (ref "C6") (pin "2") (pinfunction "2_2") (pintype "passive"))
      (node (ref "R10") (pin "1") (pinfunction "1_1") (pintype "passive"))
      (node (ref "R12") (pin "1") (pinfunction "1_1") (pintype "passive"))
      (node (ref "U$7") (pin "7") (pinfunction "B_OUT_7") (pintype "bidirectional"))
    )
    (net (code "124") (name "Net-(U$7-C_IN-)") (class "Default")
      (node (ref "R12") (pin "2") (pinfunction "2_2") (pintype "passive"))
      (node (ref "R18") (pin "2") (pinfunction "2_2") (pintype "passive"))
      (node (ref "U$7") (pin "9") (pinfunction "C_IN-_9") (pintype "bidirectional"))
    )
    (net (code "125") (name "Net-(U$7-D_IN-)") (class "Default")
      (node (ref "R11") (pin "2") (pinfunction "2_2") (pintype "passive"))
      (node (ref "R17") (pin "1") (pinfunction "1_1") (pintype "passive"))
      (node (ref "U$7") (pin "13") (pinfunction "D_IN-_13") (pintype "bidirectional"))
    )
    (net (code "126") (name "Net-(U$8-A_OUT)") (class "Default")
      (node (ref "C7") (pin "1") (pinfunction "1_1") (pintype "passive"))
      (node (ref "R19") (pin "1") (pinfunction "1_1") (pintype "passive"))
      (node (ref "R21") (pin "1") (pinfunction "1_1") (pintype "passive"))
      (node (ref "U$8") (pin "1") (pinfunction "A_OUT_1") (pintype "bidirectional"))
    )
    (net (code "127") (name "Net-(U$8-B_OUT)") (class "Default")
      (node (ref "C8") (pin "2") (pinfunction "2_2") (pintype "passive"))
      (node (ref "R20") (pin "1") (pinfunction "1_1") (pintype "passive"))
      (node (ref "R22") (pin "1") (pinfunction "1_1") (pintype "passive"))
      (node (ref "U$8") (pin "7") (pinfunction "B_OUT_7") (pintype "bidirectional"))
    )
    (net (code "128") (name "Net-(U$8-C_IN-)") (class "Default")
      (node (ref "R22") (pin "2") (pinfunction "2_2") (pintype "passive"))
      (node (ref "R24") (pin "2") (pinfunction "2_2") (pintype "passive"))
      (node (ref "U$8") (pin "9") (pinfunction "C_IN-_9") (pintype "bidirectional"))
    )
    (net (code "129") (name "Net-(U$8-D_IN-)") (class "Default")
      (node (ref "R21") (pin "2") (pinfunction "2_2") (pintype "passive"))
      (node (ref "R23") (pin "1") (pinfunction "1_1") (pintype "passive"))
      (node (ref "U$8") (pin "13") (pinfunction "D_IN-_13") (pintype "bidirectional"))
    )
    (net (code "130") (name "Net-(U$9-A_OUT)") (class "Default")
      (node (ref "C9") (pin "1") (pinfunction "1_1") (pintype "passive"))
      (node (ref "R25") (pin "1") (pinfunction "1_1") (pintype "passive"))
      (node (ref "R27") (pin "1") (pinfunction "1_1") (pintype "passive"))
      (node (ref "U$9") (pin "1") (pinfunction "A_OUT_1") (pintype "bidirectional"))
    )
    (net (code "131") (name "Net-(U$9-B_OUT)") (class "Default")
      (node (ref "C10") (pin "2") (pinfunction "2_2") (pintype "passive"))
      (node (ref "R26") (pin "1") (pinfunction "1_1") (pintype "passive"))
      (node (ref "R28") (pin "1") (pinfunction "1_1") (pintype "passive"))
      (node (ref "U$9") (pin "7") (pinfunction "B_OUT_7") (pintype "bidirectional"))
    )
    (net (code "132") (name "Net-(U$9-C_IN-)") (class "Default")
      (node (ref "R28") (pin "2") (pinfunction "2_2") (pintype "passive"))
      (node (ref "R30") (pin "2") (pinfunction "2_2") (pintype "passive"))
      (node (ref "U$9") (pin "9") (pinfunction "C_IN-_9") (pintype "bidirectional"))
    )
    (net (code "133") (name "Net-(U$9-D_IN-)") (class "Default")
      (node (ref "R27") (pin "2") (pinfunction "2_2") (pintype "passive"))
      (node (ref "R29") (pin "1") (pinfunction "1_1") (pintype "passive"))
      (node (ref "U$9") (pin "13") (pinfunction "D_IN-_13") (pintype "bidirectional"))
    )
    (net (code "134") (name "Net-(U$10-A_OUT)") (class "Default")
      (node (ref "C11") (pin "1") (pinfunction "1_1") (pintype "passive"))
      (node (ref "R31") (pin "1") (pinfunction "1_1") (pintype "passive"))
      (node (ref "R33") (pin "1") (pinfunction "1_1") (pintype "passive"))
      (node (ref "U$10") (pin "1") (pinfunction "A_OUT_1") (pintype "bidirectional"))
    )
    (net (code "135") (name "Net-(U$10-B_OUT)") (class "Default")
      (node (ref "C12") (pin "2") (pinfunction "2_2") (pintype "passive"))
      (node (ref "R32") (pin "1") (pinfunction "1_1") (pintype "passive"))
      (node (ref "R34") (pin "1") (pinfunction "1_1") (pintype "passive"))
      (node (ref "U$10") (pin "7") (pinfunction "B_OUT_7") (pintype "bidirectional"))
    )
    (net (code "136") (name "Net-(U$10-C_IN-)") (class "Default")
      (node (ref "R34") (pin "2") (pinfunction "2_2") (pintype "passive"))
      (node (ref "R36") (pin "2") (pinfunction "2_2") (pintype "passive"))
      (node (ref "U$10") (pin "9") (pinfunction "C_IN-_9") (pintype "bidirectional"))
    )
    (net (code "137") (name "Net-(U$10-D_IN-)") (class "Default")
      (node (ref "R33") (pin "2") (pinfunction "2_2") (pintype "passive"))
      (node (ref "R35") (pin "1") (pinfunction "1_1") (pintype "passive"))
      (node (ref "U$10") (pin "13") (pinfunction "D_IN-_13") (pintype "bidirectional"))
    )
    (net (code "138") (name "Net-(U$11-A_OUT)") (class "Default")
      (node (ref "C13") (pin "1") (pinfunction "1_1") (pintype "passive"))
      (node (ref "R37") (pin "1") (pinfunction "1_1") (pintype "passive"))
      (node (ref "R39") (pin "1") (pinfunction "1_1") (pintype "passive"))
      (node (ref "U$11") (pin "1") (pinfunction "A_OUT_1") (pintype "bidirectional"))
    )
    (net (code "139") (name "Net-(U$11-B_OUT)") (class "Default")
      (node (ref "C14") (pin "2") (pinfunction "2_2") (pintype "passive"))
      (node (ref "R38") (pin "1") (pinfunction "1_1") (pintype "passive"))
      (node (ref "R40") (pin "1") (pinfunction "1_1") (pintype "passive"))
      (node (ref "U$11") (pin "7") (pinfunction "B_OUT_7") (pintype "bidirectional"))
    )
    (net (code "140") (name "Net-(U$11-C_IN-)") (class "Default")
      (node (ref "R40") (pin "2") (pinfunction "2_2") (pintype "passive"))
      (node (ref "R42") (pin "2") (pinfunction "2_2") (pintype "passive"))
      (node (ref "U$11") (pin "9") (pinfunction "C_IN-_9") (pintype "bidirectional"))
    )
    (net (code "141") (name "Net-(U$11-D_IN-)") (class "Default")
      (node (ref "R39") (pin "2") (pinfunction "2_2") (pintype "passive"))
      (node (ref "R41") (pin "1") (pinfunction "1_1") (pintype "passive"))
      (node (ref "U$11") (pin "13") (pinfunction "D_IN-_13") (pintype "bidirectional"))
    )
    (net (code "142") (name "Net-(U$12-A_OUT)") (class "Default")
      (node (ref "C15") (pin "1") (pinfunction "1_1") (pintype "passive"))
      (node (ref "R43") (pin "1") (pinfunction "1_1") (pintype "passive"))
      (node (ref "R45") (pin "1") (pinfunction "1_1") (pintype "passive"))
      (node (ref "U$12") (pin "1") (pinfunction "A_OUT_1") (pintype "bidirectional"))
    )
    (net (code "143") (name "Net-(U$12-B_OUT)") (class "Default")
      (node (ref "C16") (pin "2") (pinfunction "2_2") (pintype "passive"))
      (node (ref "R44") (pin "1") (pinfunction "1_1") (pintype "passive"))
      (node (ref "R46") (pin "1") (pinfunction "1_1") (pintype "passive"))
      (node (ref "U$12") (pin "7") (pinfunction "B_OUT_7") (pintype "bidirectional"))
    )
    (net (code "144") (name "Net-(U$12-C_IN-)") (class "Default")
      (node (ref "R46") (pin "2") (pinfunction "2_2") (pintype "passive"))
      (node (ref "R48") (pin "2") (pinfunction "2_2") (pintype "passive"))
      (node (ref "U$12") (pin "9") (pinfunction "C_IN-_9") (pintype "bidirectional"))
    )
    (net (code "145") (name "Net-(U$12-D_IN-)") (class "Default")
      (node (ref "R45") (pin "2") (pinfunction "2_2") (pintype "passive"))
      (node (ref "R47") (pin "1") (pinfunction "1_1") (pintype "passive"))
      (node (ref "U$12") (pin "13") (pinfunction "D_IN-_13") (pintype "bidirectional"))
    )
    (net (code "146") (name "Net-(U$14-ENABLE)") (class "Default")
      (node (ref "R60") (pin "1") (pinfunction "1_1") (pintype "passive"))
      (node (ref "U$14") (pin "1") (pinfunction "ENABLE_1") (pintype "bidirectional"))
    )
    (net (code "147") (name "Net-(U$14-NC)") (class "Default")
      (node (ref "R59") (pin "1") (pinfunction "1_1") (pintype "passive"))
      (node (ref "U$14") (pin "4") (pinfunction "NC_4") (pintype "bidirectional"))
      (node (ref "U$14") (pin "5") (pinfunction "NC1_5") (pintype "bidirectional"))
    )
    (net (code "148") (name "Net-(U$15-1_ON)") (class "Default")
      (node (ref "R71") (pin "2") (pinfunction "2_2") (pintype "passive"))
      (node (ref "U$15") (pin "P$1") (pinfunction "1_ON_P$1") (pintype "bidirectional"))
    )
    (net (code "149") (name "Net-(U$15-2_OUT)") (class "Default")
      (node (ref "C42") (pin "1") (pinfunction "1_1") (pintype "passive"))
      (node (ref "R68") (pin "1") (pinfunction "1_1") (pintype "passive"))
      (node (ref "R69") (pin "1") (pinfunction "1_1") (pintype "passive"))
      (node (ref "R72") (pin "1") (pinfunction "1_1") (pintype "passive"))
      (node (ref "U$15") (pin "P$2") (pinfunction "2_OUT_P$2") (pintype "bidirectional"))
      (node (ref "U$16") (pin "1") (pinfunction "S1_1") (pintype "input"))
      (node (ref "U$18") (pin "P$5") (pinfunction "5V+_P$5") (pintype "bidirectional"))
    )
    (net (code "150") (name "Net-(U$15-6_SENSE)") (class "Default")
      (node (ref "R65") (pin "1") (pinfunction "1_1") (pintype "passive"))
      (node (ref "R74") (pin "1") (pinfunction "1_1") (pintype "passive"))
      (node (ref "U$15") (pin "P$6") (pinfunction "6_SENSE_P$6") (pintype "bidirectional"))
      (node (ref "U$16") (pin "7") (pinfunction "D01_7") (pintype "input"))
      (node (ref "U$16") (pin "8") (pinfunction "D1_8") (pintype "power_in"))
    )
    (net (code "151") (name "Net-(U$16-D02)") (class "Default")
      (node (ref "R72") (pin "2") (pinfunction "2_2") (pintype "passive"))
      (node (ref "U$16") (pin "5") (pinfunction "D02_5") (pintype "input"))
      (node (ref "U$16") (pin "6") (pinfunction "D2_6") (pintype "input"))
    )
    (net (code "152") (name "Net-(U$17-1_ON)") (class "Default")
      (node (ref "R79") (pin "2") (pinfunction "2_2") (pintype "passive"))
      (node (ref "U$17") (pin "P$1") (pinfunction "1_ON_P$1") (pintype "bidirectional"))
      (node (ref "U$20") (pin "E") (pinfunction "E_E") (pintype "bidirectional"))
    )
    (net (code "153") (name "Net-(U$17-6_SENSE)") (class "Default")
      (node (ref "R66") (pin "1") (pinfunction "1_1") (pintype "passive"))
      (node (ref "R82") (pin "1") (pinfunction "1_1") (pintype "passive"))
      (node (ref "U$17") (pin "P$6") (pinfunction "6_SENSE_P$6") (pintype "bidirectional"))
      (node (ref "U$19") (pin "7") (pinfunction "D01_7") (pintype "input"))
      (node (ref "U$19") (pin "8") (pinfunction "D1_8") (pintype "power_in"))
    )
    (net (code "154") (name "Net-(U$18-3IN-)") (class "Default")
      (node (ref "R69") (pin "2") (pinfunction "2_2") (pintype "passive"))
      (node (ref "U$18") (pin "P$3") (pinfunction "3IN-_P$3") (pintype "bidirectional"))
    )
    (net (code "155") (name "Net-(U$18-4IN+)") (class "Default")
      (node (ref "C41") (pin "1") (pinfunction "1_1") (pintype "passive"))
      (node (ref "R68") (pin "2") (pinfunction "2_2") (pintype "passive"))
      (node (ref "U$18") (pin "P$4") (pinfunction "4IN+_P$4") (pintype "bidirectional"))
      (node (ref "U$22") (pin "7") (pinfunction "D01_7") (pintype "input"))
      (node (ref "U$22") (pin "8") (pinfunction "D1_8") (pintype "power_in"))
    )
    (net (code "156") (name "Net-(U$19-D02)") (class "Default")
      (node (ref "R80") (pin "2") (pinfunction "2_2") (pintype "passive"))
      (node (ref "U$19") (pin "5") (pinfunction "D02_5") (pintype "input"))
      (node (ref "U$19") (pin "6") (pinfunction "D2_6") (pintype "input"))
    )
    (net (code "157") (name "Net-(U$22-S1)") (class "Default")
      (node (ref "R61") (pin "1") (pinfunction "1_1") (pintype "passive"))
      (node (ref "U$22") (pin "1") (pinfunction "S1_1") (pintype "input"))
      (node (ref "U$23") (pin "P$5") (pinfunction "5_IN_P$5") (pintype "bidirectional"))
    )
    (net (code "158") (name "Net-(U$23-7_GATE)") (class "Default")
      (node (ref "R61") (pin "2") (pinfunction "2_2") (pintype "passive"))
      (node (ref "R62") (pin "2") (pinfunction "2_2") (pintype "passive"))
      (node (ref "U$23") (pin "P$7") (pinfunction "7_GATE_P$7") (pintype "bidirectional"))
    )
    (net (code "159") (name "Net-(U$27-5_IN)") (class "Default")
      (node (ref "R62") (pin "1") (pinfunction "1_1") (pintype "passive"))
      (node (ref "R63") (pin "2") (pinfunction "2_2") (pintype "passive"))
      (node (ref "U$27") (pin "P$5") (pinfunction "5_IN_P$5") (pintype "bidirectional"))
    )
    (net (code "160") (name "Net-(U$27-7_GATE)") (class "Default")
      (node (ref "R63") (pin "1") (pinfunction "1_1") (pintype "passive"))
      (node (ref "R85") (pin "2") (pinfunction "2_2") (pintype "passive"))
      (node (ref "U$27") (pin "P$7") (pinfunction "7_GATE_P$7") (pintype "bidirectional"))
    )
    (net (code "161") (name "Net-(U1-L1)") (class "Default")
      (node (ref "L1") (pin "1") (pinfunction "1_1") (pintype "bidirectional"))
      (node (ref "U1") (pin "4") (pinfunction "L1_4") (pintype "passive"))
    )
    (net (code "162") (name "Net-(U1-L2)") (class "Default")
      (node (ref "L1") (pin "2") (pinfunction "2_2") (pintype "bidirectional"))
      (node (ref "U1") (pin "2") (pinfunction "L2_2") (pintype "passive"))
    )
    (net (code "163") (name "Net-(U2-COMP)") (class "Default")
      (node (ref "C33") (pin "1") (pinfunction "1_1") (pintype "passive"))
      (node (ref "U2") (pin "1") (pinfunction "COMP_1") (pintype "bidirectional"))
    )
    (net (code "164") (name "Net-(U2-FB)") (class "Default")
      (node (ref "R78") (pin "1") (pinfunction "1_1") (pintype "passive"))
      (node (ref "R83") (pin "2") (pinfunction "2_2") (pintype "passive"))
      (node (ref "U2") (pin "9") (pinfunction "FB_9") (pintype "input"))
    )
    (net (code "165") (name "Net-(U2-SW)") (class "Default")
      (node (ref "CR1") (pin "1") (pinfunction "1_1") (pintype "passive"))
      (node (ref "U$26") (pin "2") (pinfunction "2_2") (pintype "passive"))
      (node (ref "U2") (pin "6") (pinfunction "SW_6") (pintype "output"))
    )
    (net (code "166") (name "Net-(U2-VIN)") (class "Default")
      (node (ref "C34") (pin "1") (pinfunction "1_1") (pintype "passive"))
      (node (ref "R77") (pin "2") (pinfunction "2_2") (pintype "passive"))
      (node (ref "U2") (pin "3") (pinfunction "VIN_3") (pintype "input"))
    )
    (net (code "167") (name "Net-(U2-VREF)") (class "Default")
      (node (ref "C55") (pin "1") (pinfunction "1_1") (pintype "passive"))
      (node (ref "R83") (pin "1") (pinfunction "1_1") (pintype "passive"))
      (node (ref "U2") (pin "10") (pinfunction "VREF_10") (pintype "output"))
    )
    (net (code "168") (name "Net-(X_DRV-ISENSE)") (class "Default")
      (node (ref "R86") (pin "2") (pinfunction "2_2") (pintype "passive"))
      (node (ref "X_DRV") (pin "2") (pinfunction "ISENSE_2") (pintype "bidirectional"))
    )
    (net (code "169") (name "Net-(X_DRV1-ISENSE)") (class "Default")
      (node (ref "R89") (pin "2") (pinfunction "2_2") (pintype "passive"))
      (node (ref "X_DRV1") (pin "2") (pinfunction "ISENSE_2") (pintype "bidirectional"))
    )
    (net (code "170") (name "Net-(X_DRV2-ISENSE)") (class "Default")
      (node (ref "R92") (pin "2") (pinfunction "2_2") (pintype "passive"))
      (node (ref "X_DRV2") (pin "2") (pinfunction "ISENSE_2") (pintype "bidirectional"))
    )
    (net (code "171") (name "V+") (class "Default")
      (node (ref "C56") (pin "1") (pinfunction "1_1") (pintype "passive"))
      (node (ref "C57") (pin "1") (pinfunction "1_1") (pintype "passive"))
      (node (ref "U$10") (pin "4") (pinfunction "V+_4") (pintype "bidirectional"))
      (node (ref "U$11") (pin "4") (pinfunction "V+_4") (pintype "bidirectional"))
      (node (ref "U$12") (pin "4") (pinfunction "V+_4") (pintype "bidirectional"))
      (node (ref "U$13") (pin "1") (pinfunction "1_1") (pintype "passive"))
      (node (ref "U$5") (pin "4") (pinfunction "V+_4") (pintype "bidirectional"))
      (node (ref "U$6") (pin "4") (pinfunction "V+_4") (pintype "bidirectional"))
      (node (ref "U$7") (pin "4") (pinfunction "V+_4") (pintype "bidirectional"))
      (node (ref "U$8") (pin "4") (pinfunction "V+_4") (pintype "bidirectional"))
      (node (ref "U$9") (pin "4") (pinfunction "V+_4") (pintype "bidirectional"))
      (node (ref "U1") (pin "1") (pinfunction "VOUT_1") (pintype "power_in"))
      (node (ref "U1") (pin "10") (pinfunction "FB_10") (pintype "input"))
    )
    (net (code "172") (name "V-") (class "Default")
      (node (ref "C54") (pin "1") (pinfunction "1_1") (pintype "passive"))
      (node (ref "CR1") (pin "2") (pinfunction "2_2") (pintype "passive"))
      (node (ref "R78") (pin "2") (pinfunction "2_2") (pintype "passive"))
      (node (ref "U$10") (pin "11") (pinfunction "V-_11") (pintype "bidirectional"))
      (node (ref "U$11") (pin "11") (pinfunction "V-_11") (pintype "bidirectional"))
      (node (ref "U$12") (pin "11") (pinfunction "V-_11") (pintype "bidirectional"))
      (node (ref "U$13") (pin "2") (pinfunction "2_2") (pintype "passive"))
      (node (ref "U$5") (pin "11") (pinfunction "V-_11") (pintype "bidirectional"))
      (node (ref "U$6") (pin "11") (pinfunction "V-_11") (pintype "bidirectional"))
      (node (ref "U$7") (pin "11") (pinfunction "V-_11") (pintype "bidirectional"))
      (node (ref "U$8") (pin "11") (pinfunction "V-_11") (pintype "bidirectional"))
      (node (ref "U$9") (pin "11") (pinfunction "V-_11") (pintype "bidirectional"))
      (node (ref "U2") (pin "8") (pinfunction "OUT_8") (pintype "input"))
    )
    (net (code "173") (name "unconnected-(ADC2-CH0-Pad1)") (class "Default")
      (node (ref "ADC2") (pin "1") (pinfunction "CH0_1") (pintype "bidirectional"))
    )
    (net (code "174") (name "unconnected-(ADC2-CH1-Pad2)") (class "Default")
      (node (ref "ADC2") (pin "2") (pinfunction "CH1_2") (pintype "bidirectional"))
    )
    (net (code "175") (name "unconnected-(ADC4-CH5-Pad6)") (class "Default")
      (node (ref "ADC4") (pin "6") (pinfunction "CH5_6") (pintype "bidirectional"))
    )
    (net (code "176") (name "unconnected-(ADC4-CH6-Pad7)") (class "Default")
      (node (ref "ADC4") (pin "7") (pinfunction "CH6_7") (pintype "bidirectional"))
    )
    (net (code "177") (name "unconnected-(ADC4-CH7-Pad8)") (class "Default")
      (node (ref "ADC4") (pin "8") (pinfunction "CH7_8") (pintype "bidirectional"))
    )
    (net (code "178") (name "unconnected-(IC1-JTDI-Pad50)") (class "Default")
      (node (ref "IC1") (pin "50") (pinfunction "JTDI_50") (pintype "input"))
    )
    (net (code "179") (name "unconnected-(IC1-JTDO-Pad55)") (class "Default")
      (node (ref "IC1") (pin "55") (pinfunction "JTDO_55") (pintype "output"))
    )
    (net (code "180") (name "unconnected-(IC1-JTRST-Pad56)") (class "Default")
      (node (ref "IC1") (pin "56") (pinfunction "JTRST_56") (pintype "input"))
    )
    (net (code "181") (name "unconnected-(IC1-PA8-Pad41)") (class "Default")
      (node (ref "IC1") (pin "41") (pinfunction "PA8_41") (pintype "bidirectional"))
    )
    (net (code "182") (name "unconnected-(IC1-PA11-Pad44)") (class "Default")
      (node (ref "IC1") (pin "44") (pinfunction "PA11_44") (pintype "bidirectional"))
    )
    (net (code "183") (name "unconnected-(IC1-PA12-Pad45)") (class "Default")
      (node (ref "IC1") (pin "45") (pinfunction "PA12_45") (pintype "bidirectional"))
    )
    (net (code "184") (name "unconnected-(IC1-PB5-Pad57)") (class "Default")
      (node (ref "IC1") (pin "57") (pinfunction "PB5_57") (pintype "bidirectional"))
    )
    (net (code "185") (name "unconnected-(IC1-PB8-Pad61)") (class "Default")
      (node (ref "IC1") (pin "61") (pinfunction "PB8_61") (pintype "bidirectional"))
    )
    (net (code "186") (name "unconnected-(IC1-PB9-Pad62)") (class "Default")
      (node (ref "IC1") (pin "62") (pinfunction "PB9_62") (pintype "bidirectional"))
    )
    (net (code "187") (name "unconnected-(IC1-PB12-Pad33)") (class "Default")
      (node (ref "IC1") (pin "33") (pinfunction "PB12_33") (pintype "bidirectional"))
    )
    (net (code "188") (name "unconnected-(IC1-PB13-Pad34)") (class "Default")
      (node (ref "IC1") (pin "34") (pinfunction "PB13_34") (pintype "bidirectional"))
    )
    (net (code "189") (name "unconnected-(IC1-PB14-Pad35)") (class "Default")
      (node (ref "IC1") (pin "35") (pinfunction "PB14_35") (pintype "bidirectional"))
    )
    (net (code "190") (name "unconnected-(IC1-PB15-Pad36)") (class "Default")
      (node (ref "IC1") (pin "36") (pinfunction "PB15_36") (pintype "bidirectional"))
    )
    (net (code "191") (name "unconnected-(IC1-PC0-Pad8)") (class "Default")
      (node (ref "IC1") (pin "8") (pinfunction "PC0_8") (pintype "bidirectional"))
    )
    (net (code "192") (name "unconnected-(IC1-PC2-Pad10)") (class "Default")
      (node (ref "IC1") (pin "10") (pinfunction "PC2_10") (pintype "bidirectional"))
    )
    (net (code "193") (name "unconnected-(IC1-PC3-Pad11)") (class "Default")
      (node (ref "IC1") (pin "11") (pinfunction "PC3_11") (pintype "bidirectional"))
    )
    (net (code "194") (name "unconnected-(IC1-PC4-Pad24)") (class "Default")
      (node (ref "IC1") (pin "24") (pinfunction "PC4_24") (pintype "bidirectional"))
    )
    (net (code "195") (name "unconnected-(IC1-PD2-Pad54)") (class "Default")
      (node (ref "IC1") (pin "54") (pinfunction "PD2_54") (pintype "bidirectional"))
    )
    (net (code "196") (name "unconnected-(IC1-PH0-Pad5)") (class "Default")
      (node (ref "IC1") (pin "5") (pinfunction "PH0_5") (pintype "bidirectional"))
    )
    (net (code "197") (name "unconnected-(IC1-PH1-Pad6)") (class "Default")
      (node (ref "IC1") (pin "6") (pinfunction "PH1_6") (pintype "bidirectional"))
    )
    (net (code "198") (name "unconnected-(U$1-PadP$35)") (class "Default")
      (node (ref "U$1") (pin "P$35") (pinfunction "P$35_P$35") (pintype "bidirectional"))
    )
    (net (code "199") (name "unconnected-(U$1-PadP$37)") (class "Default")
      (node (ref "U$1") (pin "P$37") (pinfunction "P$37_P$37") (pintype "bidirectional"))
    )
    (net (code "200") (name "unconnected-(U$1-PadP$39)") (class "Default")
      (node (ref "U$1") (pin "P$39") (pinfunction "P$39_P$39") (pintype "bidirectional"))
    )
    (net (code "201") (name "unconnected-(U$1-PadP$41)") (class "Default")
      (node (ref "U$1") (pin "P$41") (pinfunction "P$41_P$41") (pintype "bidirectional"))
    )
    (net (code "202") (name "unconnected-(U$1-PadP$43)") (class "Default")
      (node (ref "U$1") (pin "P$43") (pinfunction "P$43_P$43") (pintype "bidirectional"))
    )
    (net (code "203") (name "unconnected-(U$3-NC-Pad4)") (class "Default")
      (node (ref "U$3") (pin "4") (pinfunction "NC_4") (pintype "bidirectional"))
    )
    (net (code "204") (name "unconnected-(U$4-PadINT1)") (class "Default")
      (node (ref "U$4") (pin "INT1") (pinfunction "INT1_INT1") (pintype "bidirectional"))
    )
    (net (code "205") (name "unconnected-(U$4-PadINT2)") (class "Default")
      (node (ref "U$4") (pin "INT2") (pinfunction "INT2_INT2") (pintype "bidirectional"))
    )
    (net (code "206") (name "unconnected-(U$15-8_PWRGD-PadP$8)") (class "Default")
      (node (ref "U$15") (pin "P$8") (pinfunction "8_PWRGD_P$8") (pintype "bidirectional"))
    )
    (net (code "207") (name "unconnected-(U$17-8_PWRGD-PadP$8)") (class "Default")
      (node (ref "U$17") (pin "P$8") (pinfunction "8_PWRGD_P$8") (pintype "bidirectional"))
    )
    (net (code "208") (name "unconnected-(U$21-P$3-PadP$4)") (class "Default")
      (node (ref "U$21") (pin "P$4") (pinfunction "P$3_P$4") (pintype "bidirectional"))
    )
    (net (code "209") (name "unconnected-(U$22-D02-Pad5)") (class "Default")
      (node (ref "U$22") (pin "5") (pinfunction "D02_5") (pintype "input"))
    )
    (net (code "210") (name "unconnected-(U$22-D2-Pad6)") (class "Default")
      (node (ref "U$22") (pin "6") (pinfunction "D2_6") (pintype "input"))
    )
    (net (code "211") (name "unconnected-(U$22-S2-Pad3)") (class "Default")
      (node (ref "U$22") (pin "3") (pinfunction "S2_3") (pintype "input"))
    )
    (net (code "212") (name "unconnected-(U$23-1_ON-PadP$1)") (class "Default")
      (node (ref "U$23") (pin "P$1") (pinfunction "1_ON_P$1") (pintype "bidirectional"))
    )
    (net (code "213") (name "unconnected-(U$23-2_OUT-PadP$2)") (class "Default")
      (node (ref "U$23") (pin "P$2") (pinfunction "2_OUT_P$2") (pintype "bidirectional"))
    )
    (net (code "214") (name "unconnected-(U$23-3_GATEP-PadP$3)") (class "Default")
      (node (ref "U$23") (pin "P$3") (pinfunction "3_GATEP_P$3") (pintype "bidirectional"))
    )
    (net (code "215") (name "unconnected-(U$23-4_GND-PadP$4)") (class "Default")
      (node (ref "U$23") (pin "P$4") (pinfunction "4_GND_P$4") (pintype "bidirectional"))
    )
    (net (code "216") (name "unconnected-(U$23-8_PWRGD-PadP$8)") (class "Default")
      (node (ref "U$23") (pin "P$8") (pinfunction "8_PWRGD_P$8") (pintype "bidirectional"))
    )
    (net (code "217") (name "unconnected-(U$27-1_ON-PadP$1)") (class "Default")
      (node (ref "U$27") (pin "P$1") (pinfunction "1_ON_P$1") (pintype "bidirectional"))
    )
    (net (code "218") (name "unconnected-(U$27-2_OUT-PadP$2)") (class "Default")
      (node (ref "U$27") (pin "P$2") (pinfunction "2_OUT_P$2") (pintype "bidirectional"))
    )
    (net (code "219") (name "unconnected-(U$27-3_GATEP-PadP$3)") (class "Default")
      (node (ref "U$27") (pin "P$3") (pinfunction "3_GATEP_P$3") (pintype "bidirectional"))
    )
    (net (code "220") (name "unconnected-(U$27-4_GND-PadP$4)") (class "Default")
      (node (ref "U$27") (pin "P$4") (pinfunction "4_GND_P$4") (pintype "bidirectional"))
    )
    (net (code "221") (name "unconnected-(X_DRV-VREF-Pad8)") (class "Default")
      (node (ref "X_DRV") (pin "8") (pinfunction "VREF_8") (pintype "input"))
    )
    (net (code "222") (name "unconnected-(X_DRV1-VREF-Pad8)") (class "Default")
      (node (ref "X_DRV1") (pin "8") (pinfunction "VREF_8") (pintype "input"))
    )
    (net (code "223") (name "unconnected-(X_DRV2-VREF-Pad8)") (class "Default")
      (node (ref "X_DRV2") (pin "8") (pinfunction "VREF_8") (pintype "input"))
    )
  )
)
